# DDS.net
KiCad netlist of a schematic drawn in EAGLE
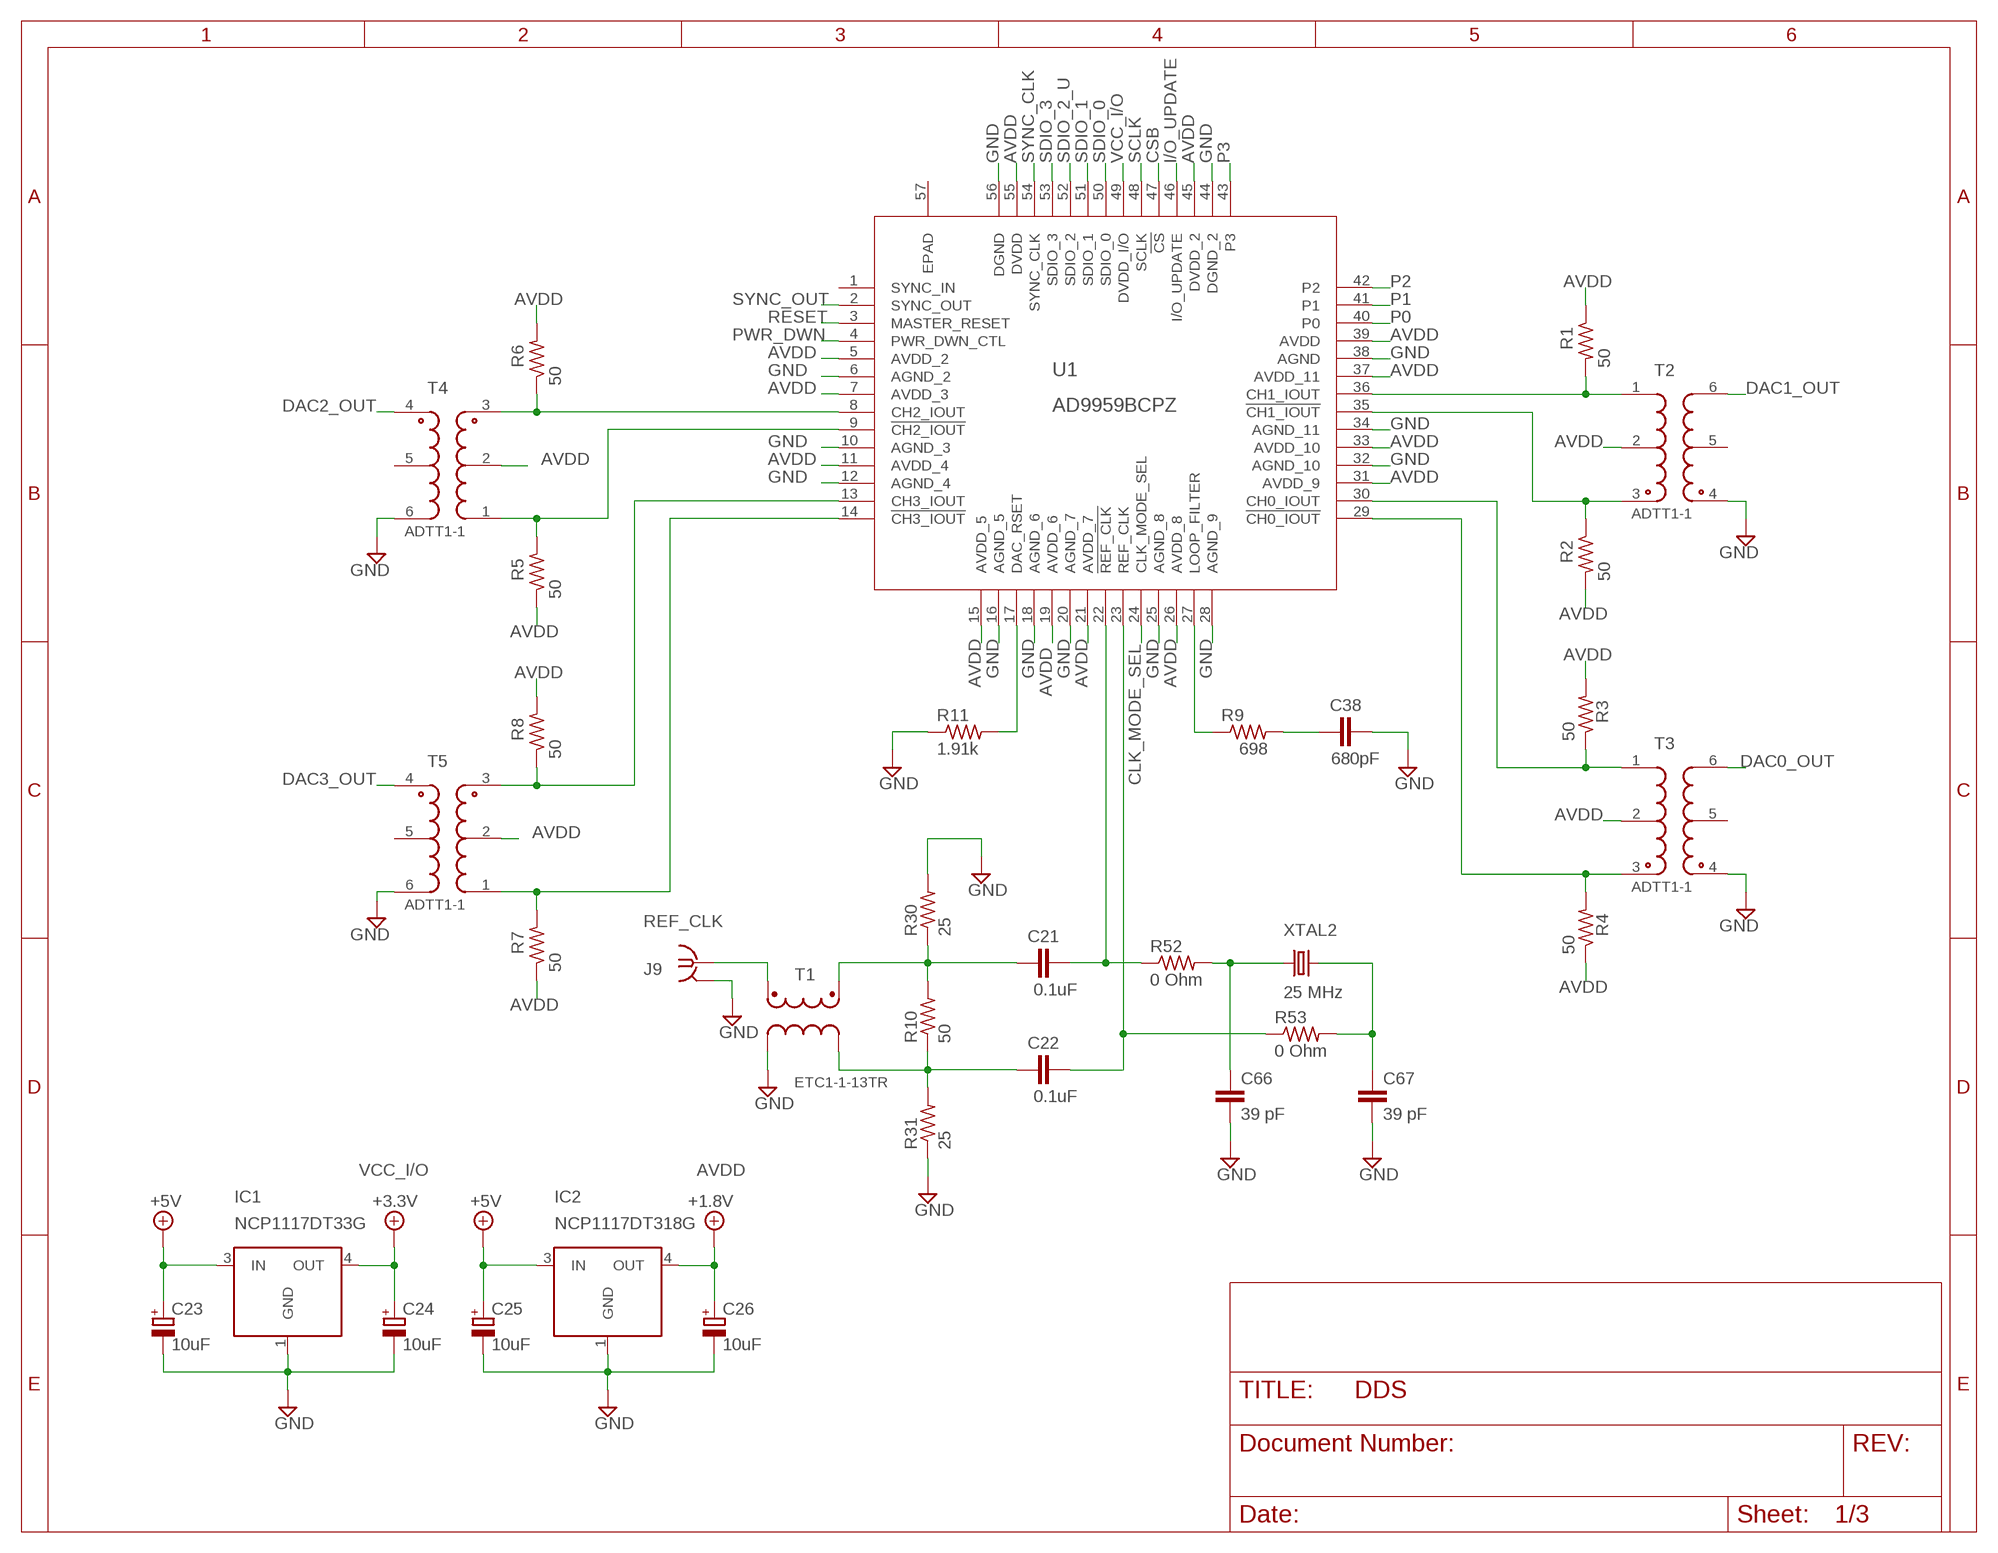
[diagram p0: schematic, sheet 1]
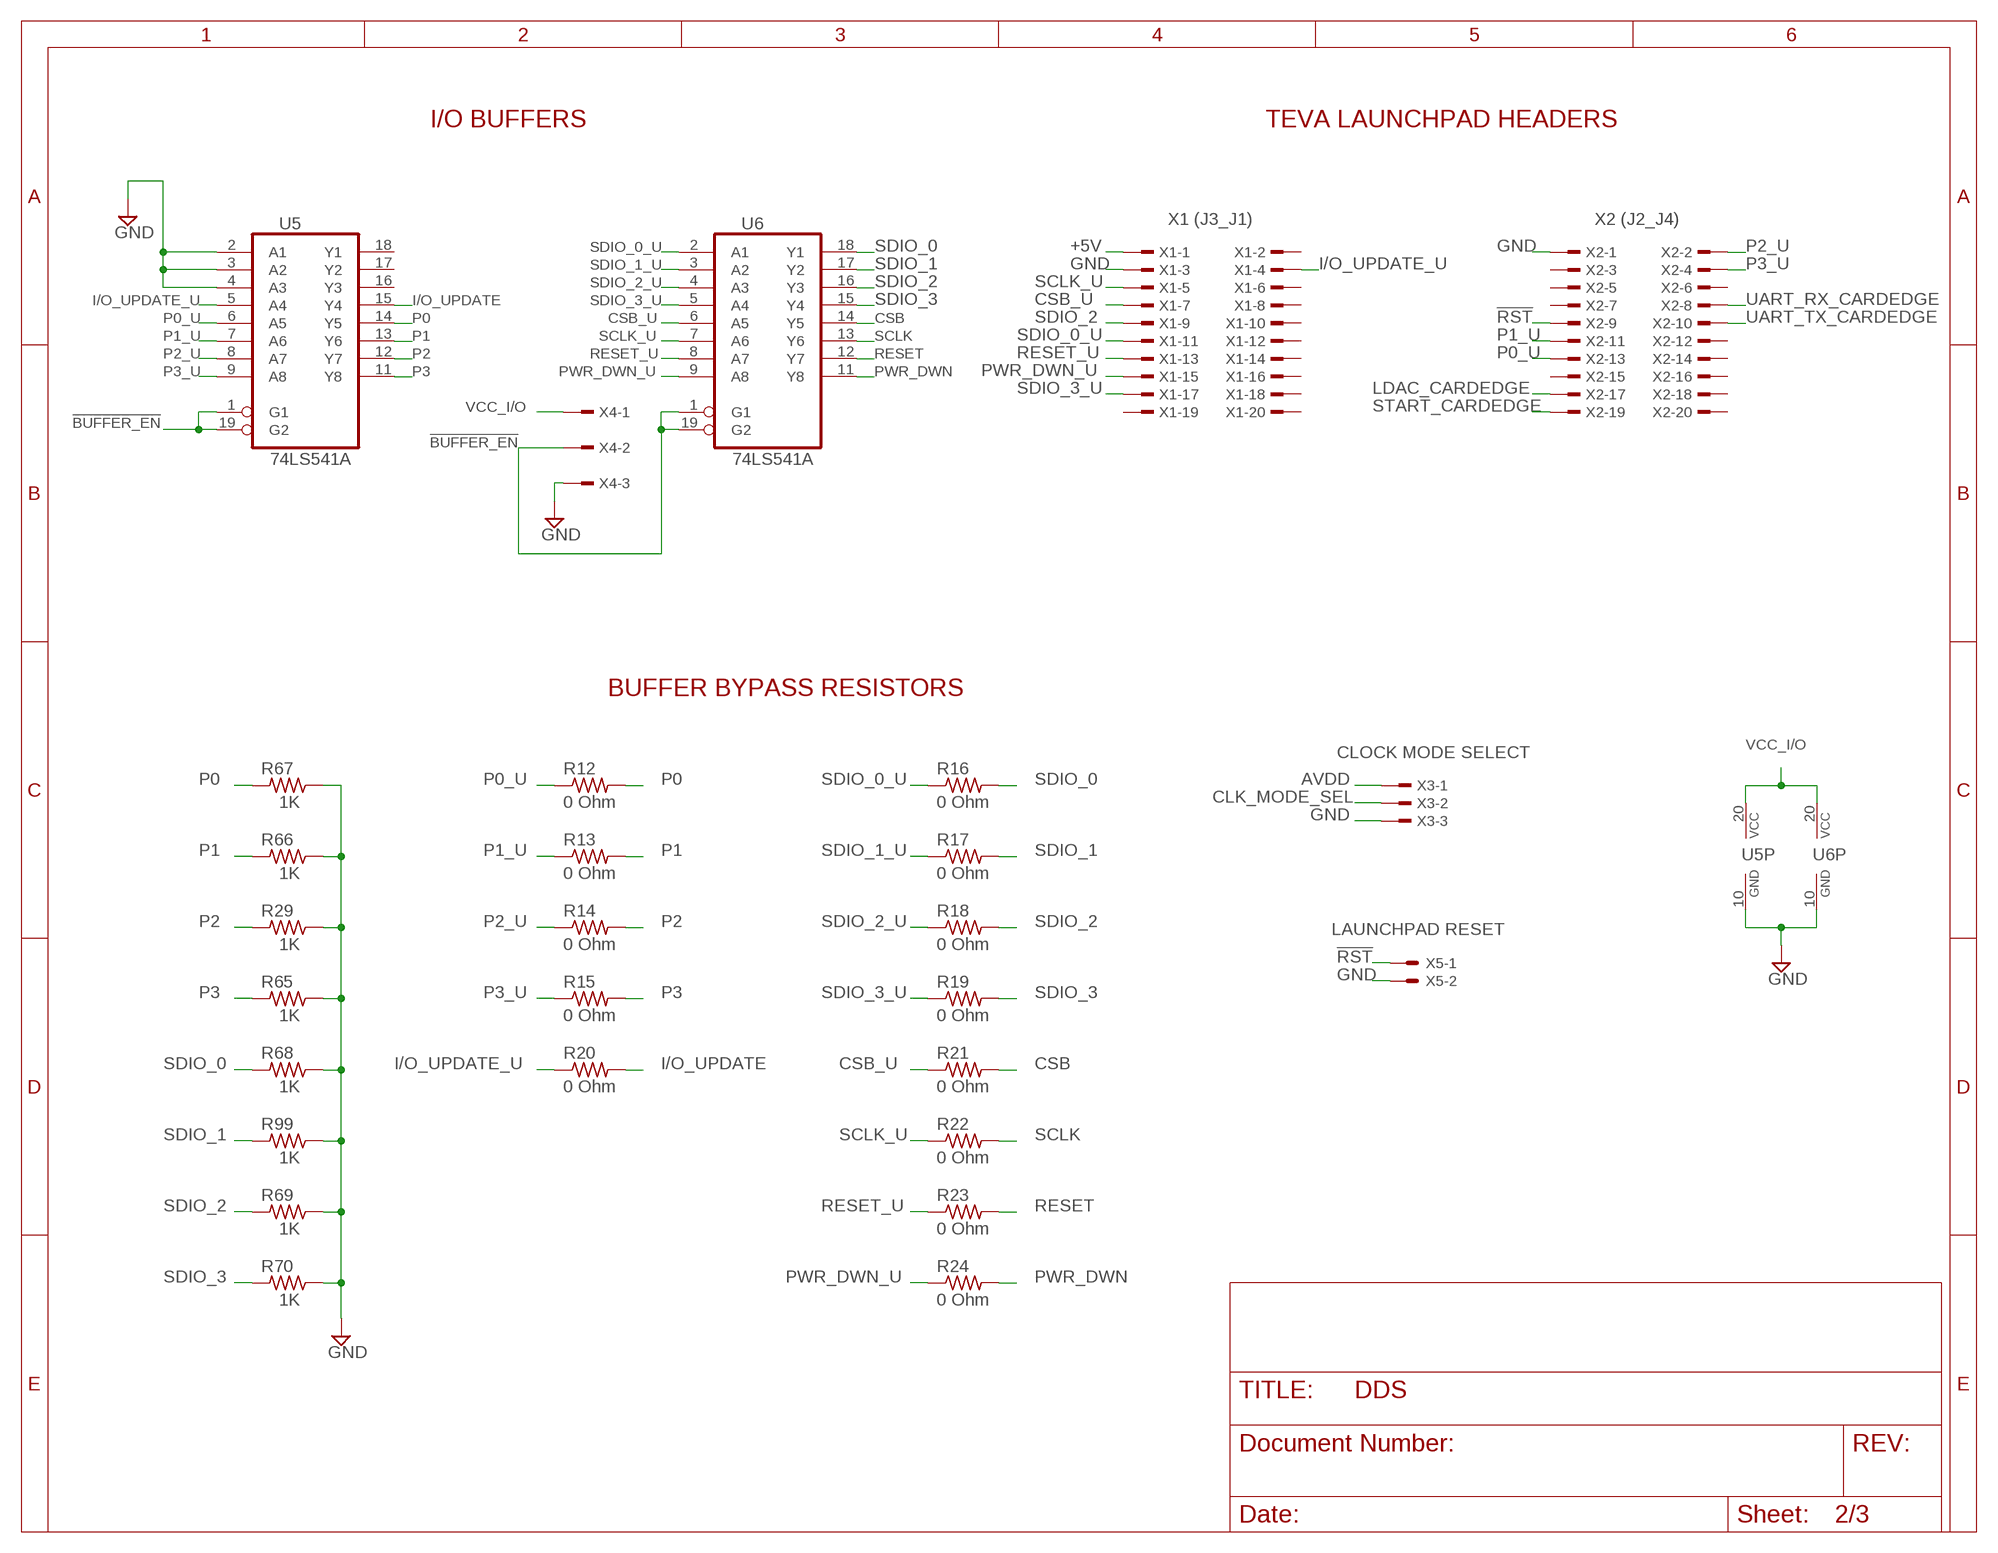
[diagram p1: schematic, sheet 2]
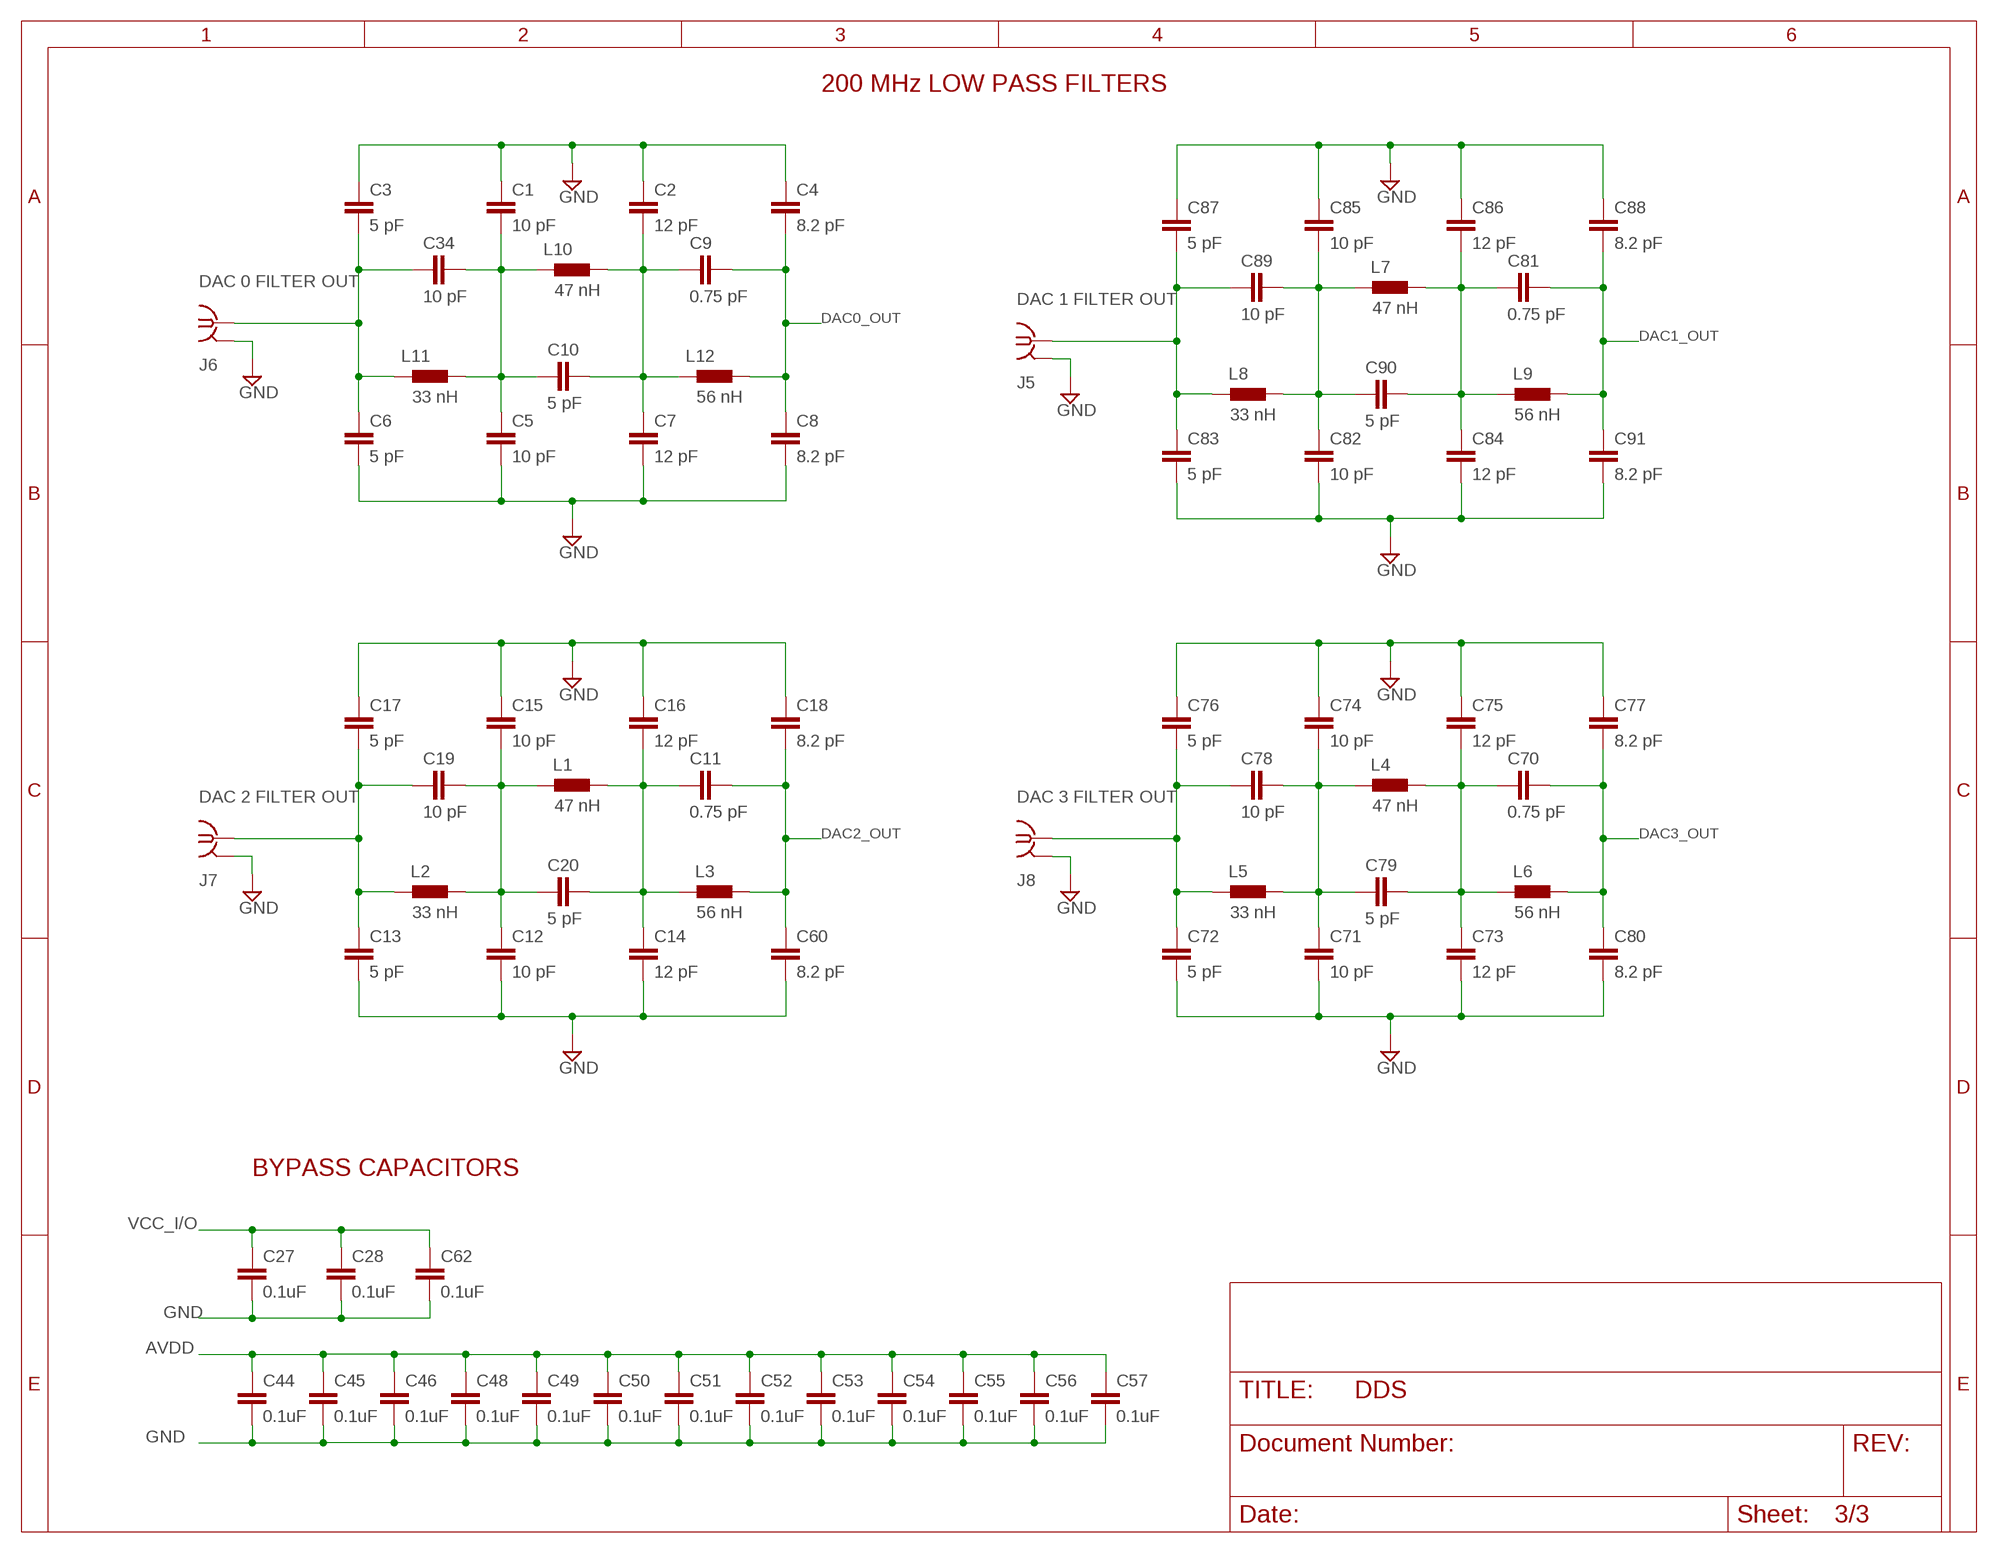
[diagram p2: schematic, sheet 3]

(export (version "E")
  (design (tool "Eeschema 10.0.6"))
  (components
    (comp (ref "C1")
      (value "10 pF")
      (footprint "eagle-import:C0402")
      (fields (field (name "MF") "SAMSUNG ELECTRO-MECHANICS") (field (name "MPN") "CL05C100JB5NNNC"))
      (libsource (lib "eagle-import") (part "C-EUC0402"))
    )
    (comp (ref "C2")
      (value "12 pF")
      (footprint "eagle-import:C0402")
      (fields (field (name "MF") "AVX") (field (name "MPN") "04025A120JAT2A"))
      (libsource (lib "eagle-import") (part "C-EUC0402"))
    )
    (comp (ref "C3")
      (value "5 pF")
      (footprint "eagle-import:C0402")
      (fields (field (name "MF") "MURATA") (field (name "MPN") "GJM1555C1H5R0CB01D"))
      (libsource (lib "eagle-import") (part "C-EUC0402"))
    )
    (comp (ref "C4")
      (value "8.2 pF")
      (footprint "eagle-import:C0402")
      (fields (field (name "MF") "AVX") (field (name "MPN") "04025A8R2BAT2A"))
      (libsource (lib "eagle-import") (part "C-EUC0402"))
    )
    (comp (ref "C5")
      (value "10 pF")
      (footprint "eagle-import:C0402")
      (fields (field (name "MF") "SAMSUNG ELECTRO-MECHANICS") (field (name "MPN") "CL05C100JB5NNNC"))
      (libsource (lib "eagle-import") (part "C-EUC0402"))
    )
    (comp (ref "C6")
      (value "5 pF")
      (footprint "eagle-import:C0402")
      (fields (field (name "MF") "MURATA") (field (name "MPN") "GJM1555C1H5R0CB01D"))
      (libsource (lib "eagle-import") (part "C-EUC0402"))
    )
    (comp (ref "C7")
      (value "12 pF")
      (footprint "eagle-import:C0402")
      (fields (field (name "MF") "AVX") (field (name "MPN") "04025A120JAT2A"))
      (libsource (lib "eagle-import") (part "C-EUC0402"))
    )
    (comp (ref "C8")
      (value "8.2 pF")
      (footprint "eagle-import:C0402")
      (fields (field (name "MF") "AVX") (field (name "MPN") "04025A8R2BAT2A"))
      (libsource (lib "eagle-import") (part "C-EUC0402"))
    )
    (comp (ref "C9")
      (value "0.75 pF")
      (footprint "eagle-import:C0402")
      (fields (field (name "MF") "MURATA") (field (name "MPN") "GJM1555C1HR75BB01D"))
      (libsource (lib "eagle-import") (part "C-EUC0402"))
    )
    (comp (ref "C10")
      (value "5 pF")
      (footprint "eagle-import:C0402")
      (fields (field (name "MF") "MURATA") (field (name "MPN") "GJM1555C1H5R0CB01D"))
      (libsource (lib "eagle-import") (part "C-EUC0402"))
    )
    (comp (ref "C11")
      (value "0.75 pF")
      (footprint "eagle-import:C0402")
      (fields (field (name "MF") "MURATA") (field (name "MPN") "GJM1555C1HR75BB01D"))
      (libsource (lib "eagle-import") (part "C-EUC0402"))
    )
    (comp (ref "C12")
      (value "10 pF")
      (footprint "eagle-import:C0402")
      (fields (field (name "MF") "SAMSUNG ELECTRO-MECHANICS") (field (name "MPN") "CL05C100JB5NNNC"))
      (libsource (lib "eagle-import") (part "C-EUC0402"))
    )
    (comp (ref "C13")
      (value "5 pF")
      (footprint "eagle-import:C0402")
      (fields (field (name "MF") "MURATA") (field (name "MPN") "GJM1555C1H5R0CB01D"))
      (libsource (lib "eagle-import") (part "C-EUC0402"))
    )
    (comp (ref "C14")
      (value "12 pF")
      (footprint "eagle-import:C0402")
      (fields (field (name "MF") "AVX") (field (name "MPN") "04025A120JAT2A"))
      (libsource (lib "eagle-import") (part "C-EUC0402"))
    )
    (comp (ref "C15")
      (value "10 pF")
      (footprint "eagle-import:C0402")
      (fields (field (name "MF") "SAMSUNG ELECTRO-MECHANICS") (field (name "MPN") "CL05C100JB5NNNC"))
      (libsource (lib "eagle-import") (part "C-EUC0402"))
    )
    (comp (ref "C16")
      (value "12 pF")
      (footprint "eagle-import:C0402")
      (fields (field (name "MF") "AVX") (field (name "MPN") "04025A120JAT2A"))
      (libsource (lib "eagle-import") (part "C-EUC0402"))
    )
    (comp (ref "C17")
      (value "5 pF")
      (footprint "eagle-import:C0402")
      (fields (field (name "MF") "MURATA") (field (name "MPN") "GJM1555C1H5R0CB01D"))
      (libsource (lib "eagle-import") (part "C-EUC0402"))
    )
    (comp (ref "C18")
      (value "8.2 pF")
      (footprint "eagle-import:C0402")
      (fields (field (name "MF") "AVX") (field (name "MPN") "04025A8R2BAT2A"))
      (libsource (lib "eagle-import") (part "C-EUC0402"))
    )
    (comp (ref "C19")
      (value "10 pF")
      (footprint "eagle-import:C0402")
      (fields (field (name "MF") "SAMSUNG ELECTRO-MECHANICS") (field (name "MPN") "CL05C100JB5NNNC"))
      (libsource (lib "eagle-import") (part "C-EUC0402"))
    )
    (comp (ref "C20")
      (value "5 pF")
      (footprint "eagle-import:C0402")
      (fields (field (name "MF") "MURATA") (field (name "MPN") "GJM1555C1H5R0CB01D"))
      (libsource (lib "eagle-import") (part "C-EUC0402"))
    )
    (comp (ref "C27")
      (value "0.1uF")
      (footprint "eagle-import:C0603")
      (fields (field (name "MF") "AVX") (field (name "MPN") "06035C104KAT2A"))
      (libsource (lib "eagle-import") (part "C-EUC0603"))
    )
    (comp (ref "C28")
      (value "0.1uF")
      (footprint "eagle-import:C0603")
      (fields (field (name "MF") "AVX") (field (name "MPN") "06035C104KAT2A"))
      (libsource (lib "eagle-import") (part "C-EUC0603"))
    )
    (comp (ref "C34")
      (value "10 pF")
      (footprint "eagle-import:C0402")
      (fields (field (name "MF") "SAMSUNG ELECTRO-MECHANICS") (field (name "MPN") "CL05C100JB5NNNC"))
      (libsource (lib "eagle-import") (part "C-EUC0402"))
    )
    (comp (ref "C44")
      (value "0.1uF")
      (footprint "eagle-import:C0402")
      (fields (field (name "MF") "KEMET") (field (name "MPN") "C0402C104K4RACTU"))
      (libsource (lib "eagle-import") (part "C-EUC0402"))
    )
    (comp (ref "C45")
      (value "0.1uF")
      (footprint "eagle-import:C0402")
      (fields (field (name "MF") "KEMET") (field (name "MPN") "C0402C104K4RACTU"))
      (libsource (lib "eagle-import") (part "C-EUC0402"))
    )
    (comp (ref "C46")
      (value "0.1uF")
      (footprint "eagle-import:C0402")
      (fields (field (name "MF") "KEMET") (field (name "MPN") "C0402C104K4RACTU"))
      (libsource (lib "eagle-import") (part "C-EUC0402"))
    )
    (comp (ref "C48")
      (value "0.1uF")
      (footprint "eagle-import:C0402")
      (fields (field (name "MF") "KEMET") (field (name "MPN") "C0402C104K4RACTU"))
      (libsource (lib "eagle-import") (part "C-EUC0402"))
    )
    (comp (ref "C49")
      (value "0.1uF")
      (footprint "eagle-import:C0402")
      (fields (field (name "MF") "KEMET") (field (name "MPN") "C0402C104K4RACTU"))
      (libsource (lib "eagle-import") (part "C-EUC0402"))
    )
    (comp (ref "C50")
      (value "0.1uF")
      (footprint "eagle-import:C0402")
      (fields (field (name "MF") "KEMET") (field (name "MPN") "C0402C104K4RACTU"))
      (libsource (lib "eagle-import") (part "C-EUC0402"))
    )
    (comp (ref "C51")
      (value "0.1uF")
      (footprint "eagle-import:C0402")
      (fields (field (name "MF") "KEMET") (field (name "MPN") "C0402C104K4RACTU"))
      (libsource (lib "eagle-import") (part "C-EUC0402"))
    )
    (comp (ref "C52")
      (value "0.1uF")
      (footprint "eagle-import:C0402")
      (fields (field (name "MF") "KEMET") (field (name "MPN") "C0402C104K4RACTU"))
      (libsource (lib "eagle-import") (part "C-EUC0402"))
    )
    (comp (ref "C53")
      (value "0.1uF")
      (footprint "eagle-import:C0402")
      (fields (field (name "MF") "KEMET") (field (name "MPN") "C0402C104K4RACTU"))
      (libsource (lib "eagle-import") (part "C-EUC0402"))
    )
    (comp (ref "C54")
      (value "0.1uF")
      (footprint "eagle-import:C0402")
      (fields (field (name "MF") "KEMET") (field (name "MPN") "C0402C104K4RACTU"))
      (libsource (lib "eagle-import") (part "C-EUC0402"))
    )
    (comp (ref "C55")
      (value "0.1uF")
      (footprint "eagle-import:C0402")
      (fields (field (name "MF") "KEMET") (field (name "MPN") "C0402C104K4RACTU"))
      (libsource (lib "eagle-import") (part "C-EUC0402"))
    )
    (comp (ref "C56")
      (value "0.1uF")
      (footprint "eagle-import:C0402")
      (fields (field (name "MF") "KEMET") (field (name "MPN") "C0402C104K4RACTU"))
      (libsource (lib "eagle-import") (part "C-EUC0402"))
    )
    (comp (ref "C57")
      (value "0.1uF")
      (footprint "eagle-import:C0402")
      (fields (field (name "MF") "KEMET") (field (name "MPN") "C0402C104K4RACTU"))
      (libsource (lib "eagle-import") (part "C-EUC0402"))
    )
    (comp (ref "C60")
      (value "8.2 pF")
      (footprint "eagle-import:C0402")
      (fields (field (name "MF") "AVX") (field (name "MPN") "04025A8R2BAT2A"))
      (libsource (lib "eagle-import") (part "C-EUC0402"))
    )
    (comp (ref "C62")
      (value "0.1uF")
      (footprint "eagle-import:C0402")
      (fields (field (name "MF") "KEMET") (field (name "MPN") "C0402C104K4RACTU"))
      (libsource (lib "eagle-import") (part "C-EUC0402"))
    )
    (comp (ref "C70")
      (value "0.75 pF")
      (footprint "eagle-import:C0402")
      (fields (field (name "MF") "MURATA") (field (name "MPN") "GJM1555C1HR75BB01D"))
      (libsource (lib "eagle-import") (part "C-EUC0402"))
    )
    (comp (ref "C71")
      (value "10 pF")
      (footprint "eagle-import:C0402")
      (fields (field (name "MF") "SAMSUNG ELECTRO-MECHANICS") (field (name "MPN") "CL05C100JB5NNNC"))
      (libsource (lib "eagle-import") (part "C-EUC0402"))
    )
    (comp (ref "C72")
      (value "5 pF")
      (footprint "eagle-import:C0402")
      (fields (field (name "MF") "MURATA") (field (name "MPN") "GJM1555C1H5R0CB01D"))
      (libsource (lib "eagle-import") (part "C-EUC0402"))
    )
    (comp (ref "C73")
      (value "12 pF")
      (footprint "eagle-import:C0402")
      (fields (field (name "MF") "AVX") (field (name "MPN") "04025A120JAT2A"))
      (libsource (lib "eagle-import") (part "C-EUC0402"))
    )
    (comp (ref "C74")
      (value "10 pF")
      (footprint "eagle-import:C0402")
      (fields (field (name "MF") "SAMSUNG ELECTRO-MECHANICS") (field (name "MPN") "CL05C100JB5NNNC"))
      (libsource (lib "eagle-import") (part "C-EUC0402"))
    )
    (comp (ref "C75")
      (value "12 pF")
      (footprint "eagle-import:C0402")
      (fields (field (name "MF") "AVX") (field (name "MPN") "04025A120JAT2A"))
      (libsource (lib "eagle-import") (part "C-EUC0402"))
    )
    (comp (ref "C76")
      (value "5 pF")
      (footprint "eagle-import:C0402")
      (fields (field (name "MF") "MURATA") (field (name "MPN") "GJM1555C1H5R0CB01D"))
      (libsource (lib "eagle-import") (part "C-EUC0402"))
    )
    (comp (ref "C77")
      (value "8.2 pF")
      (footprint "eagle-import:C0402")
      (fields (field (name "MF") "AVX") (field (name "MPN") "04025A8R2BAT2A"))
      (libsource (lib "eagle-import") (part "C-EUC0402"))
    )
    (comp (ref "C78")
      (value "10 pF")
      (footprint "eagle-import:C0402")
      (fields (field (name "MF") "SAMSUNG ELECTRO-MECHANICS") (field (name "MPN") "CL05C100JB5NNNC"))
      (libsource (lib "eagle-import") (part "C-EUC0402"))
    )
    (comp (ref "C79")
      (value "5 pF")
      (footprint "eagle-import:C0402")
      (fields (field (name "MF") "MURATA") (field (name "MPN") "GJM1555C1H5R0CB01D"))
      (libsource (lib "eagle-import") (part "C-EUC0402"))
    )
    (comp (ref "C80")
      (value "8.2 pF")
      (footprint "eagle-import:C0402")
      (fields (field (name "MF") "AVX") (field (name "MPN") "04025A8R2BAT2A"))
      (libsource (lib "eagle-import") (part "C-EUC0402"))
    )
    (comp (ref "C81")
      (value "0.75 pF")
      (footprint "eagle-import:C0402")
      (fields (field (name "MF") "MURATA") (field (name "MPN") "GJM1555C1HR75BB01D"))
      (libsource (lib "eagle-import") (part "C-EUC0402"))
    )
    (comp (ref "C82")
      (value "10 pF")
      (footprint "eagle-import:C0402")
      (fields (field (name "MF") "SAMSUNG ELECTRO-MECHANICS") (field (name "MPN") "CL05C100JB5NNNC"))
      (libsource (lib "eagle-import") (part "C-EUC0402"))
    )
    (comp (ref "C83")
      (value "5 pF")
      (footprint "eagle-import:C0402")
      (fields (field (name "MF") "MURATA") (field (name "MPN") "GJM1555C1H5R0CB01D"))
      (libsource (lib "eagle-import") (part "C-EUC0402"))
    )
    (comp (ref "C84")
      (value "12 pF")
      (footprint "eagle-import:C0402")
      (fields (field (name "MF") "AVX") (field (name "MPN") "04025A120JAT2A"))
      (libsource (lib "eagle-import") (part "C-EUC0402"))
    )
    (comp (ref "C85")
      (value "10 pF")
      (footprint "eagle-import:C0402")
      (fields (field (name "MF") "SAMSUNG ELECTRO-MECHANICS") (field (name "MPN") "CL05C100JB5NNNC"))
      (libsource (lib "eagle-import") (part "C-EUC0402"))
    )
    (comp (ref "C86")
      (value "12 pF")
      (footprint "eagle-import:C0402")
      (fields (field (name "MF") "AVX") (field (name "MPN") "04025A120JAT2A"))
      (libsource (lib "eagle-import") (part "C-EUC0402"))
    )
    (comp (ref "C87")
      (value "5 pF")
      (footprint "eagle-import:C0402")
      (fields (field (name "MF") "MURATA") (field (name "MPN") "GJM1555C1H5R0CB01D"))
      (libsource (lib "eagle-import") (part "C-EUC0402"))
    )
    (comp (ref "C88")
      (value "8.2 pF")
      (footprint "eagle-import:C0402")
      (fields (field (name "MF") "AVX") (field (name "MPN") "04025A8R2BAT2A"))
      (libsource (lib "eagle-import") (part "C-EUC0402"))
    )
    (comp (ref "C89")
      (value "10 pF")
      (footprint "eagle-import:C0402")
      (fields (field (name "MF") "SAMSUNG ELECTRO-MECHANICS") (field (name "MPN") "CL05C100JB5NNNC"))
      (libsource (lib "eagle-import") (part "C-EUC0402"))
    )
    (comp (ref "C90")
      (value "5 pF")
      (footprint "eagle-import:C0402")
      (fields (field (name "MF") "MURATA") (field (name "MPN") "GJM1555C1H5R0CB01D"))
      (libsource (lib "eagle-import") (part "C-EUC0402"))
    )
    (comp (ref "C91")
      (value "8.2 pF")
      (footprint "eagle-import:C0402")
      (fields (field (name "MF") "AVX") (field (name "MPN") "04025A8R2BAT2A"))
      (libsource (lib "eagle-import") (part "C-EUC0402"))
    )
    (comp (ref "J5")
      (value "DAC 1 FILTER OUT")
      (footprint "eagle-import:BU-SMA-V")
      (fields (field (name "MF") "JOHNSON - CINCH CONNECTIVITY") (field (name "MPN") "142-0701-231"))
      (libsource (lib "eagle-import") (part "BU-SMA-V"))
    )
    (comp (ref "J6")
      (value "DAC 0 FILTER OUT")
      (footprint "eagle-import:BU-SMA-V")
      (fields (field (name "MF") "JOHNSON - CINCH CONNECTIVITY") (field (name "MPN") "142-0701-231"))
      (libsource (lib "eagle-import") (part "BU-SMA-V"))
    )
    (comp (ref "J7")
      (value "DAC 2 FILTER OUT")
      (footprint "eagle-import:BU-SMA-V")
      (fields (field (name "MF") "JOHNSON - CINCH CONNECTIVITY") (field (name "MPN") "142-0701-231"))
      (libsource (lib "eagle-import") (part "BU-SMA-V"))
    )
    (comp (ref "J8")
      (value "DAC 3 FILTER OUT")
      (footprint "eagle-import:BU-SMA-V")
      (fields (field (name "MF") "JOHNSON - CINCH CONNECTIVITY") (field (name "MPN") "142-0701-231"))
      (libsource (lib "eagle-import") (part "BU-SMA-V"))
    )
    (comp (ref "L1")
      (value "47 nH")
      (footprint "eagle-import:0402")
      (fields (field (name "MF") "MURATA") (field (name "MPN") "LQG15HN47NJ02D"))
      (libsource (lib "eagle-import") (part "BLM15HB121SN1"))
    )
    (comp (ref "L2")
      (value "33 nH")
      (footprint "eagle-import:0402")
      (fields (field (name "MF") "MURATA") (field (name "MPN") "LQG15HS33NJ02D"))
      (libsource (lib "eagle-import") (part "BLM15HB121SN1"))
    )
    (comp (ref "L3")
      (value "56 nH")
      (footprint "eagle-import:0402")
      (fields (field (name "MF") "MURATA") (field (name "MPN") "LQG15HS56NJ02D"))
      (libsource (lib "eagle-import") (part "BLM15HB121SN1"))
    )
    (comp (ref "L4")
      (value "47 nH")
      (footprint "eagle-import:0402")
      (fields (field (name "MF") "MURATA") (field (name "MPN") "LQG15HN47NJ02D"))
      (libsource (lib "eagle-import") (part "BLM15HB121SN1"))
    )
    (comp (ref "L5")
      (value "33 nH")
      (footprint "eagle-import:0402")
      (fields (field (name "MF") "MURATA") (field (name "MPN") "LQG15HS33NJ02D"))
      (libsource (lib "eagle-import") (part "BLM15HB121SN1"))
    )
    (comp (ref "L6")
      (value "56 nH")
      (footprint "eagle-import:0402")
      (fields (field (name "MF") "MURATA") (field (name "MPN") "LQG15HS56NJ02D"))
      (libsource (lib "eagle-import") (part "BLM15HB121SN1"))
    )
    (comp (ref "L7")
      (value "47 nH")
      (footprint "eagle-import:0402")
      (fields (field (name "MF") "MURATA") (field (name "MPN") "LQG15HN47NJ02D"))
      (libsource (lib "eagle-import") (part "BLM15HB121SN1"))
    )
    (comp (ref "L8")
      (value "33 nH")
      (footprint "eagle-import:0402")
      (fields (field (name "MF") "MURATA") (field (name "MPN") "LQG15HS33NJ02D"))
      (libsource (lib "eagle-import") (part "BLM15HB121SN1"))
    )
    (comp (ref "L9")
      (value "56 nH")
      (footprint "eagle-import:0402")
      (fields (field (name "MF") "MURATA") (field (name "MPN") "LQG15HS56NJ02D"))
      (libsource (lib "eagle-import") (part "BLM15HB121SN1"))
    )
    (comp (ref "L10")
      (value "47 nH")
      (footprint "eagle-import:0402")
      (fields (field (name "MF") "MURATA") (field (name "MPN") "LQG15HN47NJ02D"))
      (libsource (lib "eagle-import") (part "BLM15HB121SN1"))
    )
    (comp (ref "L11")
      (value "33 nH")
      (footprint "eagle-import:0402")
      (fields (field (name "MF") "MURATA") (field (name "MPN") "LQG15HS33NJ02D"))
      (libsource (lib "eagle-import") (part "BLM15HB121SN1"))
    )
    (comp (ref "L12")
      (value "56 nH")
      (footprint "eagle-import:0402")
      (fields (field (name "MF") "MURATA") (field (name "MPN") "LQG15HS56NJ02D"))
      (libsource (lib "eagle-import") (part "BLM15HB121SN1"))
    )
    (comp (ref "C21")
      (value "0.1uF")
      (footprint "eagle-import:C0402")
      (fields (field (name "MF") "KEMET") (field (name "MPN") "C0402C104K4RACTU"))
      (libsource (lib "eagle-import") (part "C-EUC0402"))
    )
    (comp (ref "C22")
      (value "0.1uF")
      (footprint "eagle-import:C0402")
      (fields (field (name "MF") "KEMET") (field (name "MPN") "C0402C104K4RACTU"))
      (libsource (lib "eagle-import") (part "C-EUC0402"))
    )
    (comp (ref "C23")
      (value "10uF")
      (footprint "eagle-import:CT3528")
      (fields (field (name "MF") "KEMET") (field (name "MPN") "T494B106K025AT"))
      (libsource (lib "eagle-import") (part "CPOL-EUCT3528"))
    )
    (comp (ref "C24")
      (value "10uF")
      (footprint "eagle-import:CT3528")
      (fields (field (name "MF") "KEMET") (field (name "MPN") "T494B106K025AT"))
      (libsource (lib "eagle-import") (part "CPOL-EUCT3528"))
    )
    (comp (ref "C25")
      (value "10uF")
      (footprint "eagle-import:CT3528")
      (fields (field (name "MF") "KEMET") (field (name "MPN") "T494B106K025AT"))
      (libsource (lib "eagle-import") (part "CPOL-EUCT3528"))
    )
    (comp (ref "C26")
      (value "10uF")
      (footprint "eagle-import:CT3528")
      (fields (field (name "MF") "KEMET") (field (name "MPN") "T494B106K025AT"))
      (libsource (lib "eagle-import") (part "CPOL-EUCT3528"))
    )
    (comp (ref "C38")
      (value "680pF")
      (footprint "eagle-import:C0805")
      (fields (field (name "MF") "MULTICOMP PRO") (field (name "MPN") "MC0805N681J101CT"))
      (libsource (lib "eagle-import") (part "C-EUC0805"))
    )
    (comp (ref "C66")
      (value "39 pF")
      (footprint "eagle-import:C0805")
      (fields (field (name "MF") "MULTICOMP PRO") (field (name "MPN") "MC0805N390J500CT"))
      (libsource (lib "eagle-import") (part "C-EUC0805"))
    )
    (comp (ref "C67")
      (value "39 pF")
      (footprint "eagle-import:C0805")
      (fields (field (name "MF") "MULTICOMP PRO") (field (name "MPN") "MC0805N390J500CT"))
      (libsource (lib "eagle-import") (part "C-EUC0805"))
    )
    (comp (ref "IC1")
      (value "NCP1117DT33G")
      (footprint "eagle-import:D-PAK_TO252AA")
      (fields (field (name "MF") "ON SEMICONDUCTOR"))
      (libsource (lib "eagle-import") (part "NCP1117DT"))
    )
    (comp (ref "IC2")
      (value "NCP1117DT318G")
      (footprint "eagle-import:D-PAK_TO252AA")
      (fields (field (name "MF") "ON SEMICONDUCTOR") (field (name "MPN") "NCP1117DT18G"))
      (libsource (lib "eagle-import") (part "NCP1117DT"))
    )
    (comp (ref "J9")
      (value "REF_CLK")
      (footprint "eagle-import:BU-SMA-V")
      (fields (field (name "MF") "JOHNSON - CINCH CONNECTIVITY") (field (name "MPN") "142-0701-231"))
      (libsource (lib "eagle-import") (part "BU-SMA-V"))
    )
    (comp (ref "R1")
      (value "50")
      (footprint "eagle-import:R0603")
      (fields (field (name "MF") "VISHAY") (field (name "MPN") "CRCW060350R0FKEA"))
      (libsource (lib "eagle-import") (part "R-US_R0603"))
    )
    (comp (ref "R2")
      (value "50")
      (footprint "eagle-import:R0603")
      (fields (field (name "MF") "VISHAY") (field (name "MPN") "CRCW060350R0FKEA"))
      (libsource (lib "eagle-import") (part "R-US_R0603"))
    )
    (comp (ref "R3")
      (value "50")
      (footprint "eagle-import:R0603")
      (fields (field (name "MF") "VISHAY") (field (name "MPN") "CRCW060350R0FKEA"))
      (libsource (lib "eagle-import") (part "R-US_R0603"))
    )
    (comp (ref "R4")
      (value "50")
      (footprint "eagle-import:R0603")
      (fields (field (name "MF") "VISHAY") (field (name "MPN") "CRCW060350R0FKEA"))
      (libsource (lib "eagle-import") (part "R-US_R0603"))
    )
    (comp (ref "R5")
      (value "50")
      (footprint "eagle-import:R0603")
      (fields (field (name "MF") "VISHAY") (field (name "MPN") "CRCW060350R0FKEA"))
      (libsource (lib "eagle-import") (part "R-US_R0603"))
    )
    (comp (ref "R6")
      (value "50")
      (footprint "eagle-import:R0603")
      (fields (field (name "MF") "VISHAY") (field (name "MPN") "CRCW060350R0FKEA"))
      (libsource (lib "eagle-import") (part "R-US_R0603"))
    )
    (comp (ref "R7")
      (value "50")
      (footprint "eagle-import:R0603")
      (fields (field (name "MF") "VISHAY") (field (name "MPN") "CRCW060350R0FKEA"))
      (libsource (lib "eagle-import") (part "R-US_R0603"))
    )
    (comp (ref "R8")
      (value "50")
      (footprint "eagle-import:R0603")
      (fields (field (name "MF") "VISHAY") (field (name "MPN") "CRCW060350R0FKEA"))
      (libsource (lib "eagle-import") (part "R-US_R0603"))
    )
    (comp (ref "R9")
      (value "698")
      (footprint "eagle-import:R0603")
      (fields (field (name "MF") "PANASONIC") (field (name "MPN") "ERJ-3EKF6980V"))
      (libsource (lib "eagle-import") (part "R-US_R0603"))
    )
    (comp (ref "R10")
      (value "50")
      (footprint "eagle-import:R0603")
      (fields (field (name "MF") "VISHAY") (field (name "MPN") "CRCW060350R0FKEA"))
      (libsource (lib "eagle-import") (part "R-US_R0603"))
    )
    (comp (ref "R11")
      (value "1.91k")
      (footprint "eagle-import:R0603")
      (fields (field (name "MF") "VISHAY") (field (name "MPN") "CRCW06031K91FKEA"))
      (libsource (lib "eagle-import") (part "R-US_R0603"))
    )
    (comp (ref "R30")
      (value "25")
      (footprint "eagle-import:R0402")
      (fields (field (name "MF") "NIC COMPONENTS") (field (name "MPN") "NRC04F24R9TRF"))
      (libsource (lib "eagle-import") (part "R-US_R0402"))
    )
    (comp (ref "R31")
      (value "25")
      (footprint "eagle-import:R0402")
      (fields (field (name "MF") "NIC COMPONENTS") (field (name "MPN") "NRC04F24R9TRF"))
      (libsource (lib "eagle-import") (part "R-US_R0402"))
    )
    (comp (ref "R52")
      (value "0 Ohm")
      (footprint "eagle-import:R0402")
      (fields (field (name "MF") "PANASONIC") (field (name "MPN") "ERJ2GE0R00X"))
      (libsource (lib "eagle-import") (part "R-US_R0402"))
    )
    (comp (ref "R53")
      (value "0 Ohm")
      (footprint "eagle-import:R0402")
      (fields (field (name "MF") "PANASONIC") (field (name "MPN") "ERJ2GE0R00X"))
      (libsource (lib "eagle-import") (part "R-US_R0402"))
    )
    (comp (ref "T1")
      (value "ETC1-1-13TR")
      (footprint "eagle-import:SM22")
      (fields (field (name "MF") "M/A-Com Technology"))
      (libsource (lib "eagle-import") (part "ETC1-1-13TR"))
    )
    (comp (ref "T2")
      (value "ADTT1-1")
      (footprint "eagle-import:ADTT")
      (fields (field (name "MF") "Mini-Circuits") (field (name "MP") "ADTT1-1+"))
      (libsource (lib "eagle-import") (part "ADTT1-1"))
    )
    (comp (ref "T3")
      (value "ADTT1-1")
      (footprint "eagle-import:ADTT")
      (fields (field (name "MF") "Mini-Circuits") (field (name "MP") "ADTT1-1+"))
      (libsource (lib "eagle-import") (part "ADTT1-1"))
    )
    (comp (ref "T4")
      (value "ADTT1-1")
      (footprint "eagle-import:ADTT")
      (fields (field (name "MF") "Mini-Circuits") (field (name "MP") "ADTT1-1+"))
      (libsource (lib "eagle-import") (part "ADTT1-1"))
    )
    (comp (ref "T5")
      (value "ADTT1-1")
      (footprint "eagle-import:ADTT")
      (fields (field (name "MF") "Mini-Circuits") (field (name "MP") "ADTT1-1+"))
      (libsource (lib "eagle-import") (part "ADTT1-1"))
    )
    (comp (ref "U1")
      (value "AD9959BCPZ")
      (footprint "eagle-import:CP_56_1_ADI")
      (libsource (lib "eagle-import") (part "AD9959BCPZ"))
    )
    (comp (ref "XTAL2")
      (value "25 MHz")
      (footprint "eagle-import:HC49UP")
      (libsource (lib "eagle-import") (part "CRYSTALHC49UP"))
    )
    (comp (ref "R12")
      (value "0 Ohm")
      (footprint "eagle-import:R0402")
      (fields (field (name "MF") "PANASONIC") (field (name "MPN") "ERJ2GE0R00X"))
      (libsource (lib "eagle-import") (part "R-US_R0402"))
    )
    (comp (ref "R13")
      (value "0 Ohm")
      (footprint "eagle-import:R0402")
      (fields (field (name "MF") "PANASONIC") (field (name "MPN") "ERJ2GE0R00X"))
      (libsource (lib "eagle-import") (part "R-US_R0402"))
    )
    (comp (ref "R14")
      (value "0 Ohm")
      (footprint "eagle-import:R0402")
      (fields (field (name "MF") "PANASONIC") (field (name "MPN") "ERJ2GE0R00X"))
      (libsource (lib "eagle-import") (part "R-US_R0402"))
    )
    (comp (ref "R15")
      (value "0 Ohm")
      (footprint "eagle-import:R0402")
      (fields (field (name "MF") "PANASONIC") (field (name "MPN") "ERJ2GE0R00X"))
      (libsource (lib "eagle-import") (part "R-US_R0402"))
    )
    (comp (ref "R16")
      (value "0 Ohm")
      (footprint "eagle-import:R0402")
      (fields (field (name "MF") "PANASONIC") (field (name "MPN") "ERJ2GE0R00X"))
      (libsource (lib "eagle-import") (part "R-US_R0402"))
    )
    (comp (ref "R17")
      (value "0 Ohm")
      (footprint "eagle-import:R0402")
      (fields (field (name "MF") "PANASONIC") (field (name "MPN") "ERJ2GE0R00X"))
      (libsource (lib "eagle-import") (part "R-US_R0402"))
    )
    (comp (ref "R18")
      (value "0 Ohm")
      (footprint "eagle-import:R0402")
      (fields (field (name "MF") "PANASONIC") (field (name "MPN") "ERJ2GE0R00X"))
      (libsource (lib "eagle-import") (part "R-US_R0402"))
    )
    (comp (ref "R19")
      (value "0 Ohm")
      (footprint "eagle-import:R0402")
      (fields (field (name "MF") "PANASONIC") (field (name "MPN") "ERJ2GE0R00X"))
      (libsource (lib "eagle-import") (part "R-US_R0402"))
    )
    (comp (ref "R20")
      (value "0 Ohm")
      (footprint "eagle-import:R0402")
      (fields (field (name "MF") "PANASONIC") (field (name "MPN") "ERJ2GE0R00X"))
      (libsource (lib "eagle-import") (part "R-US_R0402"))
    )
    (comp (ref "R21")
      (value "0 Ohm")
      (footprint "eagle-import:R0402")
      (fields (field (name "MF") "PANASONIC") (field (name "MPN") "ERJ2GE0R00X"))
      (libsource (lib "eagle-import") (part "R-US_R0402"))
    )
    (comp (ref "R22")
      (value "0 Ohm")
      (footprint "eagle-import:R0402")
      (fields (field (name "MF") "PANASONIC") (field (name "MPN") "ERJ2GE0R00X"))
      (libsource (lib "eagle-import") (part "R-US_R0402"))
    )
    (comp (ref "R23")
      (value "0 Ohm")
      (footprint "eagle-import:R0402")
      (fields (field (name "MF") "PANASONIC") (field (name "MPN") "ERJ2GE0R00X"))
      (libsource (lib "eagle-import") (part "R-US_R0402"))
    )
    (comp (ref "R24")
      (value "0 Ohm")
      (footprint "eagle-import:R0402")
      (fields (field (name "MF") "PANASONIC") (field (name "MPN") "ERJ2GE0R00X"))
      (libsource (lib "eagle-import") (part "R-US_R0402"))
    )
    (comp (ref "R29")
      (value "1K")
      (footprint "eagle-import:R0603")
      (fields (field (name "MF") "PANASONIC") (field (name "MPN") "ERJ-3EKF1001V"))
      (libsource (lib "eagle-import") (part "R-US_R0603"))
    )
    (comp (ref "R65")
      (value "1K")
      (footprint "eagle-import:R0603")
      (fields (field (name "MF") "PANASONIC") (field (name "MPN") "ERJ-3EKF1001V"))
      (libsource (lib "eagle-import") (part "R-US_R0603"))
    )
    (comp (ref "R66")
      (value "1K")
      (footprint "eagle-import:R0603")
      (fields (field (name "MF") "PANASONIC") (field (name "MPN") "ERJ-3EKF1001V"))
      (libsource (lib "eagle-import") (part "R-US_R0603"))
    )
    (comp (ref "R67")
      (value "1K")
      (footprint "eagle-import:R0603")
      (fields (field (name "MF") "PANASONIC") (field (name "MPN") "ERJ-3EKF1001V"))
      (libsource (lib "eagle-import") (part "R-US_R0603"))
    )
    (comp (ref "R68")
      (value "1K")
      (footprint "eagle-import:R0603")
      (fields (field (name "MF") "PANASONIC") (field (name "MPN") "ERJ-3EKF1001V"))
      (libsource (lib "eagle-import") (part "R-US_R0603"))
    )
    (comp (ref "R69")
      (value "1K")
      (footprint "eagle-import:R0603")
      (fields (field (name "MF") "PANASONIC") (field (name "MPN") "ERJ-3EKF1001V"))
      (libsource (lib "eagle-import") (part "R-US_R0603"))
    )
    (comp (ref "R70")
      (value "1K")
      (footprint "eagle-import:R0603")
      (fields (field (name "MF") "PANASONIC") (field (name "MPN") "ERJ-3EKF1001V"))
      (libsource (lib "eagle-import") (part "R-US_R0603"))
    )
    (comp (ref "R99")
      (value "1K")
      (footprint "eagle-import:R0603")
      (fields (field (name "MF") "PANASONIC") (field (name "MPN") "ERJ-3EKF1001V"))
      (libsource (lib "eagle-import") (part "R-US_R0603"))
    )
    (comp (ref "U5")
      (value "74LS541A")
      (footprint "eagle-import:SO20W")
      (fields
        (field (name "MF") "TEXAS INSTRUMENTS")
        (field (name "MPN") "SN74LVC541APW")
        (field (name "OC_NEWARK") "29AH7649")
      )
      (libsource (lib "eagle-import") (part "74541DWLS"))
    )
    (comp (ref "U6")
      (value "74LS541A")
      (footprint "eagle-import:SO20W")
      (fields
        (field (name "MF") "TEXAS INSTRUMENTS")
        (field (name "MPN") "SN74LVC541APW")
        (field (name "OC_NEWARK") "29AH7649")
      )
      (libsource (lib "eagle-import") (part "74541DWLS"))
    )
    (comp (ref "X1")
      (value "X1 (J3_J1)")
      (footprint "eagle-import:TSW-110-XX-G-D")
      (fields
        (field (name "MF") "Samtec Inc.")
        (field (name "MPN") "TSW-110-07-G-D")
        (field (name "OC_NEWARK") "unknown")
      )
      (libsource (lib "eagle-import") (part "TSW-110--G-D07"))
    )
    (comp (ref "X2")
      (value "X2 (J2_J4)")
      (footprint "eagle-import:TSW-110-XX-G-D")
      (fields
        (field (name "MF") "Samtec Inc.")
        (field (name "MPN") "TSW-110-07-G-D")
        (field (name "OC_NEWARK") "unknown")
      )
      (libsource (lib "eagle-import") (part "TSW-110--G-D07"))
    )
    (comp (ref "X3")
      (value "CLOCK MODE SELECT")
      (footprint "eagle-import:TSW-103-XX-G-S")
      (fields
        (field (name "MF") "Samtec Inc.")
        (field (name "MPN") "TSW-103-07-G-S")
        (field (name "OC_NEWARK") "unknown")
      )
      (libsource (lib "eagle-import") (part "TSW-103--G-S08"))
    )
    (comp (ref "X4")
      (value "BUFFER")
      (footprint "eagle-import:TSW-103-XX-G-S")
      (fields
        (field (name "MF") "Samtec Inc.")
        (field (name "MPN") "TSW-103-07-G-S")
        (field (name "OC_NEWARK") "unknown")
      )
      (libsource (lib "eagle-import") (part "TSW-103--G-S08"))
    )
    (comp (ref "X5")
      (value "LAUNCHPAD RESET")
      (footprint "eagle-import:22-23-2021")
      (fields (field (name "MF") "MOLEX") (field (name "MPN") "22-23-2021"))
      (libsource (lib "eagle-import") (part "22-23-2021"))
    )
  )
  (nets
    (net (code "1") (name "+5V") (class "Default")
      (node (ref "C23") (pin "+") (pinfunction "+_+") (pintype "passive"))
      (node (ref "C25") (pin "+") (pinfunction "+_+") (pintype "passive"))
      (node (ref "IC1") (pin "3") (pinfunction "IN_3") (pintype "input"))
      (node (ref "IC2") (pin "3") (pinfunction "IN_3") (pintype "input"))
      (node (ref "X1") (pin "1") (pinfunction "1_1") (pintype "passive"))
    )
    (net (code "2") (name "AVDD") (class "Default")
      (node (ref "C26") (pin "+") (pinfunction "+_+") (pintype "passive"))
      (node (ref "C44") (pin "1") (pinfunction "1_1") (pintype "passive"))
      (node (ref "C45") (pin "1") (pinfunction "1_1") (pintype "passive"))
      (node (ref "C46") (pin "1") (pinfunction "1_1") (pintype "passive"))
      (node (ref "C48") (pin "1") (pinfunction "1_1") (pintype "passive"))
      (node (ref "C49") (pin "1") (pinfunction "1_1") (pintype "passive"))
      (node (ref "C50") (pin "1") (pinfunction "1_1") (pintype "passive"))
      (node (ref "C51") (pin "1") (pinfunction "1_1") (pintype "passive"))
      (node (ref "C52") (pin "1") (pinfunction "1_1") (pintype "passive"))
      (node (ref "C53") (pin "1") (pinfunction "1_1") (pintype "passive"))
      (node (ref "C54") (pin "1") (pinfunction "1_1") (pintype "passive"))
      (node (ref "C55") (pin "1") (pinfunction "1_1") (pintype "passive"))
      (node (ref "C56") (pin "1") (pinfunction "1_1") (pintype "passive"))
      (node (ref "C57") (pin "1") (pinfunction "1_1") (pintype "passive"))
      (node (ref "IC2") (pin "4") (pinfunction "OUT_4") (pintype "output"))
      (node (ref "R1") (pin "1") (pinfunction "1_1") (pintype "passive"))
      (node (ref "R2") (pin "2") (pinfunction "2_2") (pintype "passive"))
      (node (ref "R3") (pin "2") (pinfunction "2_2") (pintype "passive"))
      (node (ref "R4") (pin "1") (pinfunction "1_1") (pintype "passive"))
      (node (ref "R5") (pin "1") (pinfunction "1_1") (pintype "passive"))
      (node (ref "R6") (pin "2") (pinfunction "2_2") (pintype "passive"))
      (node (ref "R7") (pin "1") (pinfunction "1_1") (pintype "passive"))
      (node (ref "R8") (pin "2") (pinfunction "2_2") (pintype "passive"))
      (node (ref "T2") (pin "2") (pinfunction "PRI0_2") (pintype "passive"))
      (node (ref "T3") (pin "2") (pinfunction "PRI0_2") (pintype "passive"))
      (node (ref "T4") (pin "2") (pinfunction "PRI0_2") (pintype "passive"))
      (node (ref "T5") (pin "2") (pinfunction "PRI0_2") (pintype "passive"))
      (node (ref "U1") (pin "11") (pinfunction "AVDD_4_11") (pintype "input"))
      (node (ref "U1") (pin "15") (pinfunction "AVDD_5_15") (pintype "input"))
      (node (ref "U1") (pin "19") (pinfunction "AVDD_6_19") (pintype "input"))
      (node (ref "U1") (pin "21") (pinfunction "AVDD_7_21") (pintype "input"))
      (node (ref "U1") (pin "26") (pinfunction "AVDD_8_26") (pintype "input"))
      (node (ref "U1") (pin "31") (pinfunction "AVDD_9_31") (pintype "input"))
      (node (ref "U1") (pin "33") (pinfunction "AVDD_10_33") (pintype "input"))
      (node (ref "U1") (pin "37") (pinfunction "AVDD_11_37") (pintype "input"))
      (node (ref "U1") (pin "39") (pinfunction "AVDD_39") (pintype "input"))
      (node (ref "U1") (pin "45") (pinfunction "DVDD_2_45") (pintype "input"))
      (node (ref "U1") (pin "5") (pinfunction "AVDD_2_5") (pintype "input"))
      (node (ref "U1") (pin "55") (pinfunction "DVDD_55") (pintype "input"))
      (node (ref "U1") (pin "7") (pinfunction "AVDD_3_7") (pintype "input"))
      (node (ref "X3") (pin "1") (pinfunction "1_1") (pintype "passive"))
    )
    (net (code "3") (name "CLK_MODE_SEL") (class "Default")
      (node (ref "U1") (pin "24") (pinfunction "CLK_MODE_SEL_24") (pintype "input"))
      (node (ref "X3") (pin "2") (pinfunction "1_2") (pintype "passive"))
    )
    (net (code "4") (name "CSB") (class "Default")
      (node (ref "R21") (pin "2") (pinfunction "2_2") (pintype "passive"))
      (node (ref "U1") (pin "47") (pinfunction "~{CS}_47") (pintype "input"))
      (node (ref "U6") (pin "14") (pinfunction "Y5_14") (pintype "tri_state"))
    )
    (net (code "5") (name "CSB_U") (class "Default")
      (node (ref "R21") (pin "1") (pinfunction "1_1") (pintype "passive"))
      (node (ref "U6") (pin "6") (pinfunction "A5_6") (pintype "input"))
      (node (ref "X1") (pin "7") (pinfunction "1_7") (pintype "passive"))
    )
    (net (code "6") (name "DAC0_OUT") (class "Default")
      (node (ref "C4") (pin "2") (pinfunction "2_2") (pintype "passive"))
      (node (ref "C8") (pin "1") (pinfunction "1_1") (pintype "passive"))
      (node (ref "C9") (pin "1") (pinfunction "1_1") (pintype "passive"))
      (node (ref "L12") (pin "2") (pinfunction "2_2") (pintype "passive"))
      (node (ref "T3") (pin "6") (pinfunction "SEC-_6") (pintype "passive"))
    )
    (net (code "7") (name "DAC1_OUT") (class "Default")
      (node (ref "C81") (pin "1") (pinfunction "1_1") (pintype "passive"))
      (node (ref "C88") (pin "2") (pinfunction "2_2") (pintype "passive"))
      (node (ref "C91") (pin "1") (pinfunction "1_1") (pintype "passive"))
      (node (ref "L9") (pin "2") (pinfunction "2_2") (pintype "passive"))
      (node (ref "T2") (pin "6") (pinfunction "SEC-_6") (pintype "passive"))
    )
    (net (code "8") (name "DAC2_OUT") (class "Default")
      (node (ref "C11") (pin "1") (pinfunction "1_1") (pintype "passive"))
      (node (ref "C18") (pin "2") (pinfunction "2_2") (pintype "passive"))
      (node (ref "C60") (pin "1") (pinfunction "1_1") (pintype "passive"))
      (node (ref "L3") (pin "2") (pinfunction "2_2") (pintype "passive"))
      (node (ref "T4") (pin "4") (pinfunction "SEC+_4") (pintype "passive"))
    )
    (net (code "9") (name "DAC3_OUT") (class "Default")
      (node (ref "C70") (pin "1") (pinfunction "1_1") (pintype "passive"))
      (node (ref "C77") (pin "2") (pinfunction "2_2") (pintype "passive"))
      (node (ref "C80") (pin "1") (pinfunction "1_1") (pintype "passive"))
      (node (ref "L6") (pin "2") (pinfunction "2_2") (pintype "passive"))
      (node (ref "T5") (pin "4") (pinfunction "SEC+_4") (pintype "passive"))
    )
    (net (code "10") (name "GND") (class "Default")
      (node (ref "C1") (pin "1") (pinfunction "1_1") (pintype "passive"))
      (node (ref "C12") (pin "2") (pinfunction "2_2") (pintype "passive"))
      (node (ref "C13") (pin "2") (pinfunction "2_2") (pintype "passive"))
      (node (ref "C14") (pin "2") (pinfunction "2_2") (pintype "passive"))
      (node (ref "C15") (pin "1") (pinfunction "1_1") (pintype "passive"))
      (node (ref "C16") (pin "1") (pinfunction "1_1") (pintype "passive"))
      (node (ref "C17") (pin "1") (pinfunction "1_1") (pintype "passive"))
      (node (ref "C18") (pin "1") (pinfunction "1_1") (pintype "passive"))
      (node (ref "C2") (pin "1") (pinfunction "1_1") (pintype "passive"))
      (node (ref "C23") (pin "-") (pinfunction "-_-") (pintype "passive"))
      (node (ref "C24") (pin "-") (pinfunction "-_-") (pintype "passive"))
      (node (ref "C25") (pin "-") (pinfunction "-_-") (pintype "passive"))
      (node (ref "C26") (pin "-") (pinfunction "-_-") (pintype "passive"))
      (node (ref "C27") (pin "2") (pinfunction "2_2") (pintype "passive"))
      (node (ref "C28") (pin "2") (pinfunction "2_2") (pintype "passive"))
      (node (ref "C3") (pin "1") (pinfunction "1_1") (pintype "passive"))
      (node (ref "C38") (pin "2") (pinfunction "2_2") (pintype "passive"))
      (node (ref "C4") (pin "1") (pinfunction "1_1") (pintype "passive"))
      (node (ref "C44") (pin "2") (pinfunction "2_2") (pintype "passive"))
      (node (ref "C45") (pin "2") (pinfunction "2_2") (pintype "passive"))
      (node (ref "C46") (pin "2") (pinfunction "2_2") (pintype "passive"))
      (node (ref "C48") (pin "2") (pinfunction "2_2") (pintype "passive"))
      (node (ref "C49") (pin "2") (pinfunction "2_2") (pintype "passive"))
      (node (ref "C5") (pin "2") (pinfunction "2_2") (pintype "passive"))
      (node (ref "C50") (pin "2") (pinfunction "2_2") (pintype "passive"))
      (node (ref "C51") (pin "2") (pinfunction "2_2") (pintype "passive"))
      (node (ref "C52") (pin "2") (pinfunction "2_2") (pintype "passive"))
      (node (ref "C53") (pin "2") (pinfunction "2_2") (pintype "passive"))
      (node (ref "C54") (pin "2") (pinfunction "2_2") (pintype "passive"))
      (node (ref "C55") (pin "2") (pinfunction "2_2") (pintype "passive"))
      (node (ref "C56") (pin "2") (pinfunction "2_2") (pintype "passive"))
      (node (ref "C57") (pin "2") (pinfunction "2_2") (pintype "passive"))
      (node (ref "C6") (pin "2") (pinfunction "2_2") (pintype "passive"))
      (node (ref "C60") (pin "2") (pinfunction "2_2") (pintype "passive"))
      (node (ref "C62") (pin "2") (pinfunction "2_2") (pintype "passive"))
      (node (ref "C66") (pin "2") (pinfunction "2_2") (pintype "passive"))
      (node (ref "C67") (pin "2") (pinfunction "2_2") (pintype "passive"))
      (node (ref "C7") (pin "2") (pinfunction "2_2") (pintype "passive"))
      (node (ref "C71") (pin "2") (pinfunction "2_2") (pintype "passive"))
      (node (ref "C72") (pin "2") (pinfunction "2_2") (pintype "passive"))
      (node (ref "C73") (pin "2") (pinfunction "2_2") (pintype "passive"))
      (node (ref "C74") (pin "1") (pinfunction "1_1") (pintype "passive"))
      (node (ref "C75") (pin "1") (pinfunction "1_1") (pintype "passive"))
      (node (ref "C76") (pin "1") (pinfunction "1_1") (pintype "passive"))
      (node (ref "C77") (pin "1") (pinfunction "1_1") (pintype "passive"))
      (node (ref "C8") (pin "2") (pinfunction "2_2") (pintype "passive"))
      (node (ref "C80") (pin "2") (pinfunction "2_2") (pintype "passive"))
      (node (ref "C82") (pin "2") (pinfunction "2_2") (pintype "passive"))
      (node (ref "C83") (pin "2") (pinfunction "2_2") (pintype "passive"))
      (node (ref "C84") (pin "2") (pinfunction "2_2") (pintype "passive"))
      (node (ref "C85") (pin "1") (pinfunction "1_1") (pintype "passive"))
      (node (ref "C86") (pin "1") (pinfunction "1_1") (pintype "passive"))
      (node (ref "C87") (pin "1") (pinfunction "1_1") (pintype "passive"))
      (node (ref "C88") (pin "1") (pinfunction "1_1") (pintype "passive"))
      (node (ref "C91") (pin "2") (pinfunction "2_2") (pintype "passive"))
      (node (ref "IC1") (pin "1") (pinfunction "GND_1") (pintype "power_in"))
      (node (ref "IC2") (pin "1") (pinfunction "GND_1") (pintype "power_in"))
      (node (ref "J5") (pin "2") (pinfunction "GND_2") (pintype "power_in"))
      (node (ref "J6") (pin "2") (pinfunction "GND_2") (pintype "power_in"))
      (node (ref "J7") (pin "2") (pinfunction "GND_2") (pintype "power_in"))
      (node (ref "J8") (pin "2") (pinfunction "GND_2") (pintype "power_in"))
      (node (ref "J9") (pin "2") (pinfunction "GND_2") (pintype "power_in"))
      (node (ref "R11") (pin "1") (pinfunction "1_1") (pintype "passive"))
      (node (ref "R29") (pin "1") (pinfunction "1_1") (pintype "passive"))
      (node (ref "R30") (pin "2") (pinfunction "2_2") (pintype "passive"))
      (node (ref "R31") (pin "1") (pinfunction "1_1") (pintype "passive"))
      (node (ref "R65") (pin "1") (pinfunction "1_1") (pintype "passive"))
      (node (ref "R66") (pin "1") (pinfunction "1_1") (pintype "passive"))
      (node (ref "R67") (pin "1") (pinfunction "1_1") (pintype "passive"))
      (node (ref "R68") (pin "1") (pinfunction "1_1") (pintype "passive"))
      (node (ref "R69") (pin "1") (pinfunction "1_1") (pintype "passive"))
      (node (ref "R70") (pin "1") (pinfunction "1_1") (pintype "passive"))
      (node (ref "R99") (pin "1") (pinfunction "1_1") (pintype "passive"))
      (node (ref "T1") (pin "4") (pinfunction "4_4") (pintype "passive"))
      (node (ref "T2") (pin "4") (pinfunction "SEC+_4") (pintype "passive"))
      (node (ref "T3") (pin "4") (pinfunction "SEC+_4") (pintype "passive"))
      (node (ref "T4") (pin "6") (pinfunction "SEC-_6") (pintype "passive"))
      (node (ref "T5") (pin "6") (pinfunction "SEC-_6") (pintype "passive"))
      (node (ref "U1") (pin "10") (pinfunction "AGND_3_10") (pintype "input"))
      (node (ref "U1") (pin "12") (pinfunction "AGND_4_12") (pintype "input"))
      (node (ref "U1") (pin "16") (pinfunction "AGND_5_16") (pintype "input"))
      (node (ref "U1") (pin "18") (pinfunction "AGND_6_18") (pintype "input"))
      (node (ref "U1") (pin "20") (pinfunction "AGND_7_20") (pintype "input"))
      (node (ref "U1") (pin "25") (pinfunction "AGND_8_25") (pintype "input"))
      (node (ref "U1") (pin "28") (pinfunction "AGND_9_28") (pintype "input"))
      (node (ref "U1") (pin "32") (pinfunction "AGND_10_32") (pintype "input"))
      (node (ref "U1") (pin "34") (pinfunction "AGND_11_34") (pintype "input"))
      (node (ref "U1") (pin "38") (pinfunction "AGND_38") (pintype "input"))
      (node (ref "U1") (pin "44") (pinfunction "DGND_2_44") (pintype "input"))
      (node (ref "U1") (pin "56") (pinfunction "DGND_56") (pintype "input"))
      (node (ref "U1") (pin "6") (pinfunction "AGND_2_6") (pintype "input"))
      (node (ref "U5") (pin "10") (pinfunction "GND_10") (pintype "power_in"))
      (node (ref "U5") (pin "2") (pinfunction "A1_2") (pintype "input"))
      (node (ref "U5") (pin "3") (pinfunction "A2_3") (pintype "input"))
      (node (ref "U5") (pin "4") (pinfunction "A3_4") (pintype "input"))
      (node (ref "U6") (pin "10") (pinfunction "GND_10") (pintype "power_in"))
      (node (ref "X1") (pin "3") (pinfunction "1_3") (pintype "passive"))
      (node (ref "X2") (pin "1") (pinfunction "1_1") (pintype "passive"))
      (node (ref "X3") (pin "3") (pinfunction "1_3") (pintype "passive"))
      (node (ref "X4") (pin "3") (pinfunction "1_3") (pintype "passive"))
      (node (ref "X5") (pin "2") (pinfunction "S_2") (pintype "passive"))
    )
    (net (code "11") (name "I{slash}O_UPDATE") (class "Default")
      (node (ref "R20") (pin "2") (pinfunction "2_2") (pintype "passive"))
      (node (ref "U1") (pin "46") (pinfunction "I/O_UPDATE_46") (pintype "input"))
      (node (ref "U5") (pin "15") (pinfunction "Y4_15") (pintype "tri_state"))
    )
    (net (code "12") (name "I{slash}O_UPDATE_U") (class "Default")
      (node (ref "R20") (pin "1") (pinfunction "1_1") (pintype "passive"))
      (node (ref "U5") (pin "5") (pinfunction "A4_5") (pintype "input"))
      (node (ref "X1") (pin "4") (pinfunction "1_4") (pintype "passive"))
    )
    (net (code "13") (name "LDAC_CARDEDGE") (class "Default")
      (node (ref "X2") (pin "17") (pinfunction "1_17") (pintype "passive"))
    )
    (net (code "14") (name "Net-(C1-Pad2)") (class "Default")
      (node (ref "C1") (pin "2") (pinfunction "2_2") (pintype "passive"))
      (node (ref "C10") (pin "2") (pinfunction "2_2") (pintype "passive"))
      (node (ref "C34") (pin "1") (pinfunction "1_1") (pintype "passive"))
      (node (ref "C5") (pin "1") (pinfunction "1_1") (pintype "passive"))
      (node (ref "L10") (pin "1") (pinfunction "1_1") (pintype "passive"))
      (node (ref "L11") (pin "2") (pinfunction "2_2") (pintype "passive"))
    )
    (net (code "15") (name "Net-(C3-Pad2)") (class "Default")
      (node (ref "C3") (pin "2") (pinfunction "2_2") (pintype "passive"))
      (node (ref "C34") (pin "2") (pinfunction "2_2") (pintype "passive"))
      (node (ref "C6") (pin "1") (pinfunction "1_1") (pintype "passive"))
      (node (ref "J6") (pin "1") (pinfunction "1_1") (pintype "passive"))
      (node (ref "L11") (pin "1") (pinfunction "1_1") (pintype "passive"))
    )
    (net (code "16") (name "Net-(C10-Pad1)") (class "Default")
      (node (ref "C10") (pin "1") (pinfunction "1_1") (pintype "passive"))
      (node (ref "C2") (pin "2") (pinfunction "2_2") (pintype "passive"))
      (node (ref "C7") (pin "1") (pinfunction "1_1") (pintype "passive"))
      (node (ref "C9") (pin "2") (pinfunction "2_2") (pintype "passive"))
      (node (ref "L10") (pin "2") (pinfunction "2_2") (pintype "passive"))
      (node (ref "L12") (pin "1") (pinfunction "1_1") (pintype "passive"))
    )
    (net (code "17") (name "Net-(C11-Pad2)") (class "Default")
      (node (ref "C11") (pin "2") (pinfunction "2_2") (pintype "passive"))
      (node (ref "C14") (pin "1") (pinfunction "1_1") (pintype "passive"))
      (node (ref "C16") (pin "2") (pinfunction "2_2") (pintype "passive"))
      (node (ref "C20") (pin "1") (pinfunction "1_1") (pintype "passive"))
      (node (ref "L1") (pin "2") (pinfunction "2_2") (pintype "passive"))
      (node (ref "L3") (pin "1") (pinfunction "1_1") (pintype "passive"))
    )
    (net (code "18") (name "Net-(C12-Pad1)") (class "Default")
      (node (ref "C12") (pin "1") (pinfunction "1_1") (pintype "passive"))
      (node (ref "C15") (pin "2") (pinfunction "2_2") (pintype "passive"))
      (node (ref "C19") (pin "1") (pinfunction "1_1") (pintype "passive"))
      (node (ref "C20") (pin "2") (pinfunction "2_2") (pintype "passive"))
      (node (ref "L1") (pin "1") (pinfunction "1_1") (pintype "passive"))
      (node (ref "L2") (pin "2") (pinfunction "2_2") (pintype "passive"))
    )
    (net (code "19") (name "Net-(C13-Pad1)") (class "Default")
      (node (ref "C13") (pin "1") (pinfunction "1_1") (pintype "passive"))
      (node (ref "C17") (pin "2") (pinfunction "2_2") (pintype "passive"))
      (node (ref "C19") (pin "2") (pinfunction "2_2") (pintype "passive"))
      (node (ref "J7") (pin "1") (pinfunction "1_1") (pintype "passive"))
      (node (ref "L2") (pin "1") (pinfunction "1_1") (pintype "passive"))
    )
    (net (code "20") (name "Net-(C21-Pad1)") (class "Default")
      (node (ref "C21") (pin "1") (pinfunction "1_1") (pintype "passive"))
      (node (ref "R10") (pin "2") (pinfunction "2_2") (pintype "passive"))
      (node (ref "R30") (pin "1") (pinfunction "1_1") (pintype "passive"))
      (node (ref "T1") (pin "1") (pinfunction "1_1") (pintype "passive"))
    )
    (net (code "21") (name "Net-(C22-Pad1)") (class "Default")
      (node (ref "C22") (pin "1") (pinfunction "1_1") (pintype "passive"))
      (node (ref "R10") (pin "1") (pinfunction "1_1") (pintype "passive"))
      (node (ref "R31") (pin "2") (pinfunction "2_2") (pintype "passive"))
      (node (ref "T1") (pin "3") (pinfunction "3_3") (pintype "passive"))
    )
    (net (code "22") (name "Net-(C38-Pad1)") (class "Default")
      (node (ref "C38") (pin "1") (pinfunction "1_1") (pintype "passive"))
      (node (ref "R9") (pin "2") (pinfunction "2_2") (pintype "passive"))
    )
    (net (code "23") (name "Net-(C66-Pad1)") (class "Default")
      (node (ref "C66") (pin "1") (pinfunction "1_1") (pintype "passive"))
      (node (ref "R52") (pin "2") (pinfunction "2_2") (pintype "passive"))
      (node (ref "XTAL2") (pin "1") (pinfunction "1_1") (pintype "passive"))
    )
    (net (code "24") (name "Net-(C67-Pad1)") (class "Default")
      (node (ref "C67") (pin "1") (pinfunction "1_1") (pintype "passive"))
      (node (ref "R53") (pin "2") (pinfunction "2_2") (pintype "passive"))
      (node (ref "XTAL2") (pin "2") (pinfunction "2_2") (pintype "passive"))
    )
    (net (code "25") (name "Net-(C70-Pad2)") (class "Default")
      (node (ref "C70") (pin "2") (pinfunction "2_2") (pintype "passive"))
      (node (ref "C73") (pin "1") (pinfunction "1_1") (pintype "passive"))
      (node (ref "C75") (pin "2") (pinfunction "2_2") (pintype "passive"))
      (node (ref "C79") (pin "1") (pinfunction "1_1") (pintype "passive"))
      (node (ref "L4") (pin "2") (pinfunction "2_2") (pintype "passive"))
      (node (ref "L6") (pin "1") (pinfunction "1_1") (pintype "passive"))
    )
    (net (code "26") (name "Net-(C71-Pad1)") (class "Default")
      (node (ref "C71") (pin "1") (pinfunction "1_1") (pintype "passive"))
      (node (ref "C74") (pin "2") (pinfunction "2_2") (pintype "passive"))
      (node (ref "C78") (pin "1") (pinfunction "1_1") (pintype "passive"))
      (node (ref "C79") (pin "2") (pinfunction "2_2") (pintype "passive"))
      (node (ref "L4") (pin "1") (pinfunction "1_1") (pintype "passive"))
      (node (ref "L5") (pin "2") (pinfunction "2_2") (pintype "passive"))
    )
    (net (code "27") (name "Net-(C72-Pad1)") (class "Default")
      (node (ref "C72") (pin "1") (pinfunction "1_1") (pintype "passive"))
      (node (ref "C76") (pin "2") (pinfunction "2_2") (pintype "passive"))
      (node (ref "C78") (pin "2") (pinfunction "2_2") (pintype "passive"))
      (node (ref "J8") (pin "1") (pinfunction "1_1") (pintype "passive"))
      (node (ref "L5") (pin "1") (pinfunction "1_1") (pintype "passive"))
    )
    (net (code "28") (name "Net-(C81-Pad2)") (class "Default")
      (node (ref "C81") (pin "2") (pinfunction "2_2") (pintype "passive"))
      (node (ref "C84") (pin "1") (pinfunction "1_1") (pintype "passive"))
      (node (ref "C86") (pin "2") (pinfunction "2_2") (pintype "passive"))
      (node (ref "C90") (pin "1") (pinfunction "1_1") (pintype "passive"))
      (node (ref "L7") (pin "2") (pinfunction "2_2") (pintype "passive"))
      (node (ref "L9") (pin "1") (pinfunction "1_1") (pintype "passive"))
    )
    (net (code "29") (name "Net-(C82-Pad1)") (class "Default")
      (node (ref "C82") (pin "1") (pinfunction "1_1") (pintype "passive"))
      (node (ref "C85") (pin "2") (pinfunction "2_2") (pintype "passive"))
      (node (ref "C89") (pin "1") (pinfunction "1_1") (pintype "passive"))
      (node (ref "C90") (pin "2") (pinfunction "2_2") (pintype "passive"))
      (node (ref "L7") (pin "1") (pinfunction "1_1") (pintype "passive"))
      (node (ref "L8") (pin "2") (pinfunction "2_2") (pintype "passive"))
    )
    (net (code "30") (name "Net-(C83-Pad1)") (class "Default")
      (node (ref "C83") (pin "1") (pinfunction "1_1") (pintype "passive"))
      (node (ref "C87") (pin "2") (pinfunction "2_2") (pintype "passive"))
      (node (ref "C89") (pin "2") (pinfunction "2_2") (pintype "passive"))
      (node (ref "J5") (pin "1") (pinfunction "1_1") (pintype "passive"))
      (node (ref "L8") (pin "1") (pinfunction "1_1") (pintype "passive"))
    )
    (net (code "31") (name "Net-(J9-Pad1)") (class "Default")
      (node (ref "J9") (pin "1") (pinfunction "1_1") (pintype "passive"))
      (node (ref "T1") (pin "5") (pinfunction "5_5") (pintype "passive"))
    )
    (net (code "32") (name "Net-(T2-PRI+)") (class "Default")
      (node (ref "R2") (pin "1") (pinfunction "1_1") (pintype "passive"))
      (node (ref "T2") (pin "3") (pinfunction "PRI+_3") (pintype "passive"))
      (node (ref "U1") (pin "35") (pinfunction "~{CH1_IOUT}_35") (pintype "output"))
    )
    (net (code "33") (name "Net-(T2-PRI-)") (class "Default")
      (node (ref "R1") (pin "2") (pinfunction "2_2") (pintype "passive"))
      (node (ref "T2") (pin "1") (pinfunction "PRI-_1") (pintype "passive"))
      (node (ref "U1") (pin "36") (pinfunction "CH1_IOUT_36") (pintype "output"))
    )
    (net (code "34") (name "Net-(T3-PRI+)") (class "Default")
      (node (ref "R4") (pin "2") (pinfunction "2_2") (pintype "passive"))
      (node (ref "T3") (pin "3") (pinfunction "PRI+_3") (pintype "passive"))
      (node (ref "U1") (pin "29") (pinfunction "~{CH0_IOUT}_29") (pintype "output"))
    )
    (net (code "35") (name "Net-(T3-PRI-)") (class "Default")
      (node (ref "R3") (pin "1") (pinfunction "1_1") (pintype "passive"))
      (node (ref "T3") (pin "1") (pinfunction "PRI-_1") (pintype "passive"))
      (node (ref "U1") (pin "30") (pinfunction "CH0_IOUT_30") (pintype "output"))
    )
    (net (code "36") (name "Net-(T4-PRI+)") (class "Default")
      (node (ref "R6") (pin "1") (pinfunction "1_1") (pintype "passive"))
      (node (ref "T4") (pin "3") (pinfunction "PRI+_3") (pintype "passive"))
      (node (ref "U1") (pin "8") (pinfunction "CH2_IOUT_8") (pintype "output"))
    )
    (net (code "37") (name "Net-(T4-PRI-)") (class "Default")
      (node (ref "R5") (pin "2") (pinfunction "2_2") (pintype "passive"))
      (node (ref "T4") (pin "1") (pinfunction "PRI-_1") (pintype "passive"))
      (node (ref "U1") (pin "9") (pinfunction "~{CH2_IOUT}_9") (pintype "output"))
    )
    (net (code "38") (name "Net-(T5-PRI+)") (class "Default")
      (node (ref "R8") (pin "1") (pinfunction "1_1") (pintype "passive"))
      (node (ref "T5") (pin "3") (pinfunction "PRI+_3") (pintype "passive"))
      (node (ref "U1") (pin "13") (pinfunction "CH3_IOUT_13") (pintype "output"))
    )
    (net (code "39") (name "Net-(T5-PRI-)") (class "Default")
      (node (ref "R7") (pin "2") (pinfunction "2_2") (pintype "passive"))
      (node (ref "T5") (pin "1") (pinfunction "PRI-_1") (pintype "passive"))
      (node (ref "U1") (pin "14") (pinfunction "~{CH3_IOUT}_14") (pintype "output"))
    )
    (net (code "40") (name "Net-(U1-DAC_RSET)") (class "Default")
      (node (ref "R11") (pin "2") (pinfunction "2_2") (pintype "passive"))
      (node (ref "U1") (pin "17") (pinfunction "DAC_RSET_17") (pintype "input"))
    )
    (net (code "41") (name "Net-(U1-LOOP_FILTER)") (class "Default")
      (node (ref "R9") (pin "1") (pinfunction "1_1") (pintype "passive"))
      (node (ref "U1") (pin "27") (pinfunction "LOOP_FILTER_27") (pintype "input"))
    )
    (net (code "42") (name "Net-(U1-REF_CLK)") (class "Default")
      (node (ref "C22") (pin "2") (pinfunction "2_2") (pintype "passive"))
      (node (ref "R53") (pin "1") (pinfunction "1_1") (pintype "passive"))
      (node (ref "U1") (pin "23") (pinfunction "REF_CLK_23") (pintype "input"))
    )
    (net (code "43") (name "Net-(U1-~{REF_CLK})") (class "Default")
      (node (ref "C21") (pin "2") (pinfunction "2_2") (pintype "passive"))
      (node (ref "R52") (pin "1") (pinfunction "1_1") (pintype "passive"))
      (node (ref "U1") (pin "22") (pinfunction "~{REF_CLK}_22") (pintype "input"))
    )
    (net (code "44") (name "P0") (class "Default")
      (node (ref "R12") (pin "2") (pinfunction "2_2") (pintype "passive"))
      (node (ref "R67") (pin "2") (pinfunction "2_2") (pintype "passive"))
      (node (ref "U1") (pin "40") (pinfunction "P0_40") (pintype "input"))
      (node (ref "U5") (pin "14") (pinfunction "Y5_14") (pintype "tri_state"))
    )
    (net (code "45") (name "P0_U") (class "Default")
      (node (ref "R12") (pin "1") (pinfunction "1_1") (pintype "passive"))
      (node (ref "U5") (pin "6") (pinfunction "A5_6") (pintype "input"))
      (node (ref "X2") (pin "13") (pinfunction "1_13") (pintype "passive"))
    )
    (net (code "46") (name "P1") (class "Default")
      (node (ref "R13") (pin "2") (pinfunction "2_2") (pintype "passive"))
      (node (ref "R66") (pin "2") (pinfunction "2_2") (pintype "passive"))
      (node (ref "U1") (pin "41") (pinfunction "P1_41") (pintype "input"))
      (node (ref "U5") (pin "13") (pinfunction "Y6_13") (pintype "tri_state"))
    )
    (net (code "47") (name "P1_U") (class "Default")
      (node (ref "R13") (pin "1") (pinfunction "1_1") (pintype "passive"))
      (node (ref "U5") (pin "7") (pinfunction "A6_7") (pintype "input"))
      (node (ref "X2") (pin "11") (pinfunction "1_11") (pintype "passive"))
    )
    (net (code "48") (name "P2") (class "Default")
      (node (ref "R14") (pin "2") (pinfunction "2_2") (pintype "passive"))
      (node (ref "R29") (pin "2") (pinfunction "2_2") (pintype "passive"))
      (node (ref "U1") (pin "42") (pinfunction "P2_42") (pintype "input"))
      (node (ref "U5") (pin "12") (pinfunction "Y7_12") (pintype "tri_state"))
    )
    (net (code "49") (name "P2_U") (class "Default")
      (node (ref "R14") (pin "1") (pinfunction "1_1") (pintype "passive"))
      (node (ref "U5") (pin "8") (pinfunction "A7_8") (pintype "input"))
      (node (ref "X2") (pin "2") (pinfunction "1_2") (pintype "passive"))
    )
    (net (code "50") (name "P3") (class "Default")
      (node (ref "R15") (pin "2") (pinfunction "2_2") (pintype "passive"))
      (node (ref "R65") (pin "2") (pinfunction "2_2") (pintype "passive"))
      (node (ref "U1") (pin "43") (pinfunction "P3_43") (pintype "input"))
      (node (ref "U5") (pin "11") (pinfunction "Y8_11") (pintype "tri_state"))
    )
    (net (code "51") (name "P3_U") (class "Default")
      (node (ref "R15") (pin "1") (pinfunction "1_1") (pintype "passive"))
      (node (ref "U5") (pin "9") (pinfunction "A8_9") (pintype "input"))
      (node (ref "X2") (pin "4") (pinfunction "1_4") (pintype "passive"))
    )
    (net (code "52") (name "PWR_DWN") (class "Default")
      (node (ref "R24") (pin "2") (pinfunction "2_2") (pintype "passive"))
      (node (ref "U1") (pin "4") (pinfunction "PWR_DWN_CTL_4") (pintype "input"))
      (node (ref "U6") (pin "11") (pinfunction "Y8_11") (pintype "tri_state"))
    )
    (net (code "53") (name "PWR_DWN_U") (class "Default")
      (node (ref "R24") (pin "1") (pinfunction "1_1") (pintype "passive"))
      (node (ref "U6") (pin "9") (pinfunction "A8_9") (pintype "input"))
      (node (ref "X1") (pin "15") (pinfunction "1_15") (pintype "passive"))
    )
    (net (code "54") (name "RESET") (class "Default")
      (node (ref "R23") (pin "2") (pinfunction "2_2") (pintype "passive"))
      (node (ref "U1") (pin "3") (pinfunction "MASTER_RESET_3") (pintype "input"))
      (node (ref "U6") (pin "12") (pinfunction "Y7_12") (pintype "tri_state"))
    )
    (net (code "55") (name "RESET_U") (class "Default")
      (node (ref "R23") (pin "1") (pinfunction "1_1") (pintype "passive"))
      (node (ref "U6") (pin "8") (pinfunction "A7_8") (pintype "input"))
      (node (ref "X1") (pin "13") (pinfunction "1_13") (pintype "passive"))
    )
    (net (code "56") (name "SCLK") (class "Default")
      (node (ref "R22") (pin "2") (pinfunction "2_2") (pintype "passive"))
      (node (ref "U1") (pin "48") (pinfunction "SCLK_48") (pintype "input"))
      (node (ref "U6") (pin "13") (pinfunction "Y6_13") (pintype "tri_state"))
    )
    (net (code "57") (name "SCLK_U") (class "Default")
      (node (ref "R22") (pin "1") (pinfunction "1_1") (pintype "passive"))
      (node (ref "U6") (pin "7") (pinfunction "A6_7") (pintype "input"))
      (node (ref "X1") (pin "5") (pinfunction "1_5") (pintype "passive"))
    )
    (net (code "58") (name "SDIO_0") (class "Default")
      (node (ref "R16") (pin "2") (pinfunction "2_2") (pintype "passive"))
      (node (ref "R68") (pin "2") (pinfunction "2_2") (pintype "passive"))
      (node (ref "U1") (pin "50") (pinfunction "SDIO_0_50") (pintype "bidirectional"))
      (node (ref "U6") (pin "18") (pinfunction "Y1_18") (pintype "tri_state"))
    )
    (net (code "59") (name "SDIO_0_U") (class "Default")
      (node (ref "R16") (pin "1") (pinfunction "1_1") (pintype "passive"))
      (node (ref "U6") (pin "2") (pinfunction "A1_2") (pintype "input"))
      (node (ref "X1") (pin "11") (pinfunction "1_11") (pintype "passive"))
    )
    (net (code "60") (name "SDIO_1") (class "Default")
      (node (ref "R17") (pin "2") (pinfunction "2_2") (pintype "passive"))
      (node (ref "R99") (pin "2") (pinfunction "2_2") (pintype "passive"))
      (node (ref "U1") (pin "51") (pinfunction "SDIO_1_51") (pintype "bidirectional"))
      (node (ref "U6") (pin "17") (pinfunction "Y2_17") (pintype "tri_state"))
    )
    (net (code "61") (name "SDIO_1_U") (class "Default")
      (node (ref "R17") (pin "1") (pinfunction "1_1") (pintype "passive"))
      (node (ref "U6") (pin "3") (pinfunction "A2_3") (pintype "input"))
    )
    (net (code "62") (name "SDIO_2") (class "Default")
      (node (ref "R18") (pin "2") (pinfunction "2_2") (pintype "passive"))
      (node (ref "R69") (pin "2") (pinfunction "2_2") (pintype "passive"))
      (node (ref "U6") (pin "16") (pinfunction "Y3_16") (pintype "tri_state"))
      (node (ref "X1") (pin "9") (pinfunction "1_9") (pintype "passive"))
    )
    (net (code "63") (name "SDIO_2_U") (class "Default")
      (node (ref "R18") (pin "1") (pinfunction "1_1") (pintype "passive"))
      (node (ref "U1") (pin "52") (pinfunction "SDIO_2_52") (pintype "bidirectional"))
      (node (ref "U6") (pin "4") (pinfunction "A3_4") (pintype "input"))
    )
    (net (code "64") (name "SDIO_3") (class "Default")
      (node (ref "R19") (pin "2") (pinfunction "2_2") (pintype "passive"))
      (node (ref "R70") (pin "2") (pinfunction "2_2") (pintype "passive"))
      (node (ref "U1") (pin "53") (pinfunction "SDIO_3_53") (pintype "bidirectional"))
      (node (ref "U6") (pin "15") (pinfunction "Y4_15") (pintype "tri_state"))
    )
    (net (code "65") (name "SDIO_3_U") (class "Default")
      (node (ref "R19") (pin "1") (pinfunction "1_1") (pintype "passive"))
      (node (ref "U6") (pin "5") (pinfunction "A4_5") (pintype "input"))
      (node (ref "X1") (pin "17") (pinfunction "1_17") (pintype "passive"))
    )
    (net (code "66") (name "START_CARDEDGE") (class "Default")
      (node (ref "X2") (pin "19") (pinfunction "1_19") (pintype "passive"))
    )
    (net (code "67") (name "SYNC_CLK") (class "Default")
      (node (ref "U1") (pin "54") (pinfunction "SYNC_CLK_54") (pintype "output"))
    )
    (net (code "68") (name "SYNC_OUT") (class "Default")
      (node (ref "U1") (pin "2") (pinfunction "SYNC_OUT_2") (pintype "output"))
    )
    (net (code "69") (name "UART_RX_CARDEDGE") (class "Default")
      (node (ref "X2") (pin "8") (pinfunction "1_8") (pintype "passive"))
    )
    (net (code "70") (name "UART_TX_CARDEDGE") (class "Default")
      (node (ref "X2") (pin "10") (pinfunction "1_10") (pintype "passive"))
    )
    (net (code "71") (name "VCC_I{slash}O") (class "Default")
      (node (ref "C24") (pin "+") (pinfunction "+_+") (pintype "passive"))
      (node (ref "C27") (pin "1") (pinfunction "1_1") (pintype "passive"))
      (node (ref "C28") (pin "1") (pinfunction "1_1") (pintype "passive"))
      (node (ref "C62") (pin "1") (pinfunction "1_1") (pintype "passive"))
      (node (ref "IC1") (pin "4") (pinfunction "OUT_4") (pintype "output"))
      (node (ref "U1") (pin "49") (pinfunction "DVDD_I/O_49") (pintype "input"))
      (node (ref "U5") (pin "20") (pinfunction "VCC_20") (pintype "power_in"))
      (node (ref "U6") (pin "20") (pinfunction "VCC_20") (pintype "power_in"))
      (node (ref "X4") (pin "1") (pinfunction "1_1") (pintype "passive"))
    )
    (net (code "72") (name "unconnected-(T2-SEC0-Pad5)") (class "Default")
      (node (ref "T2") (pin "5") (pinfunction "SEC0_5") (pintype "passive"))
    )
    (net (code "73") (name "unconnected-(T3-SEC0-Pad5)") (class "Default")
      (node (ref "T3") (pin "5") (pinfunction "SEC0_5") (pintype "passive"))
    )
    (net (code "74") (name "unconnected-(T4-SEC0-Pad5)") (class "Default")
      (node (ref "T4") (pin "5") (pinfunction "SEC0_5") (pintype "passive"))
    )
    (net (code "75") (name "unconnected-(T5-SEC0-Pad5)") (class "Default")
      (node (ref "T5") (pin "5") (pinfunction "SEC0_5") (pintype "passive"))
    )
    (net (code "76") (name "unconnected-(U1-EPAD-Pad57)") (class "Default")
      (node (ref "U1") (pin "57") (pinfunction "EPAD_57") (pintype "passive"))
    )
    (net (code "77") (name "unconnected-(U1-SYNC_IN-Pad1)") (class "Default")
      (node (ref "U1") (pin "1") (pinfunction "SYNC_IN_1") (pintype "input"))
    )
    (net (code "78") (name "unconnected-(U5A-Y1-Pad18)") (class "Default")
      (node (ref "U5") (pin "18") (pinfunction "Y1_18") (pintype "tri_state"))
    )
    (net (code "79") (name "unconnected-(U5A-Y2-Pad17)") (class "Default")
      (node (ref "U5") (pin "17") (pinfunction "Y2_17") (pintype "tri_state"))
    )
    (net (code "80") (name "unconnected-(U5A-Y3-Pad16)") (class "Default")
      (node (ref "U5") (pin "16") (pinfunction "Y3_16") (pintype "tri_state"))
    )
    (net (code "81") (name "unconnected-(X1B-1-Pad10)") (class "Default")
      (node (ref "X1") (pin "10") (pinfunction "1_10") (pintype "passive"))
    )
    (net (code "82") (name "unconnected-(X1D-1-Pad12)") (class "Default")
      (node (ref "X1") (pin "12") (pinfunction "1_12") (pintype "passive"))
    )
    (net (code "83") (name "unconnected-(X1F-1-Pad14)") (class "Default")
      (node (ref "X1") (pin "14") (pinfunction "1_14") (pintype "passive"))
    )
    (net (code "84") (name "unconnected-(X1H-1-Pad16)") (class "Default")
      (node (ref "X1") (pin "16") (pinfunction "1_16") (pintype "passive"))
    )
    (net (code "85") (name "unconnected-(X1J-1-Pad18)") (class "Default")
      (node (ref "X1") (pin "18") (pinfunction "1_18") (pintype "passive"))
    )
    (net (code "86") (name "unconnected-(X1K-1-Pad19)") (class "Default")
      (node (ref "X1") (pin "19") (pinfunction "1_19") (pintype "passive"))
    )
    (net (code "87") (name "unconnected-(X1L-1-Pad2)") (class "Default")
      (node (ref "X1") (pin "2") (pinfunction "1_2") (pintype "passive"))
    )
    (net (code "88") (name "unconnected-(X1M-1-Pad20)") (class "Default")
      (node (ref "X1") (pin "20") (pinfunction "1_20") (pintype "passive"))
    )
    (net (code "89") (name "unconnected-(X1Q-1-Pad6)") (class "Default")
      (node (ref "X1") (pin "6") (pinfunction "1_6") (pintype "passive"))
    )
    (net (code "90") (name "unconnected-(X1S-1-Pad8)") (class "Default")
      (node (ref "X1") (pin "8") (pinfunction "1_8") (pintype "passive"))
    )
    (net (code "91") (name "unconnected-(X2D-1-Pad12)") (class "Default")
      (node (ref "X2") (pin "12") (pinfunction "1_12") (pintype "passive"))
    )
    (net (code "92") (name "unconnected-(X2F-1-Pad14)") (class "Default")
      (node (ref "X2") (pin "14") (pinfunction "1_14") (pintype "passive"))
    )
    (net (code "93") (name "unconnected-(X2G-1-Pad15)") (class "Default")
      (node (ref "X2") (pin "15") (pinfunction "1_15") (pintype "passive"))
    )
    (net (code "94") (name "unconnected-(X2H-1-Pad16)") (class "Default")
      (node (ref "X2") (pin "16") (pinfunction "1_16") (pintype "passive"))
    )
    (net (code "95") (name "unconnected-(X2J-1-Pad18)") (class "Default")
      (node (ref "X2") (pin "18") (pinfunction "1_18") (pintype "passive"))
    )
    (net (code "96") (name "unconnected-(X2M-1-Pad20)") (class "Default")
      (node (ref "X2") (pin "20") (pinfunction "1_20") (pintype "passive"))
    )
    (net (code "97") (name "unconnected-(X2N-1-Pad3)") (class "Default")
      (node (ref "X2") (pin "3") (pinfunction "1_3") (pintype "passive"))
    )
    (net (code "98") (name "unconnected-(X2P-1-Pad5)") (class "Default")
      (node (ref "X2") (pin "5") (pinfunction "1_5") (pintype "passive"))
    )
    (net (code "99") (name "unconnected-(X2Q-1-Pad6)") (class "Default")
      (node (ref "X2") (pin "6") (pinfunction "1_6") (pintype "passive"))
    )
    (net (code "100") (name "unconnected-(X2R-1-Pad7)") (class "Default")
      (node (ref "X2") (pin "7") (pinfunction "1_7") (pintype "passive"))
    )
    (net (code "101") (name "~{BUFFER_EN}") (class "Default")
      (node (ref "U5") (pin "1") (pinfunction "G1_1") (pintype "input"))
      (node (ref "U5") (pin "19") (pinfunction "G2_19") (pintype "input"))
      (node (ref "U6") (pin "1") (pinfunction "G1_1") (pintype "input"))
      (node (ref "U6") (pin "19") (pinfunction "G2_19") (pintype "input"))
      (node (ref "X4") (pin "2") (pinfunction "1_2") (pintype "passive"))
    )
    (net (code "102") (name "~{RST}") (class "Default")
      (node (ref "X2") (pin "9") (pinfunction "1_9") (pintype "passive"))
      (node (ref "X5") (pin "1") (pinfunction "S_1") (pintype "passive"))
    )
  )
)
